# PowerPCB.net
KiCad netlist of a schematic drawn in EAGLE
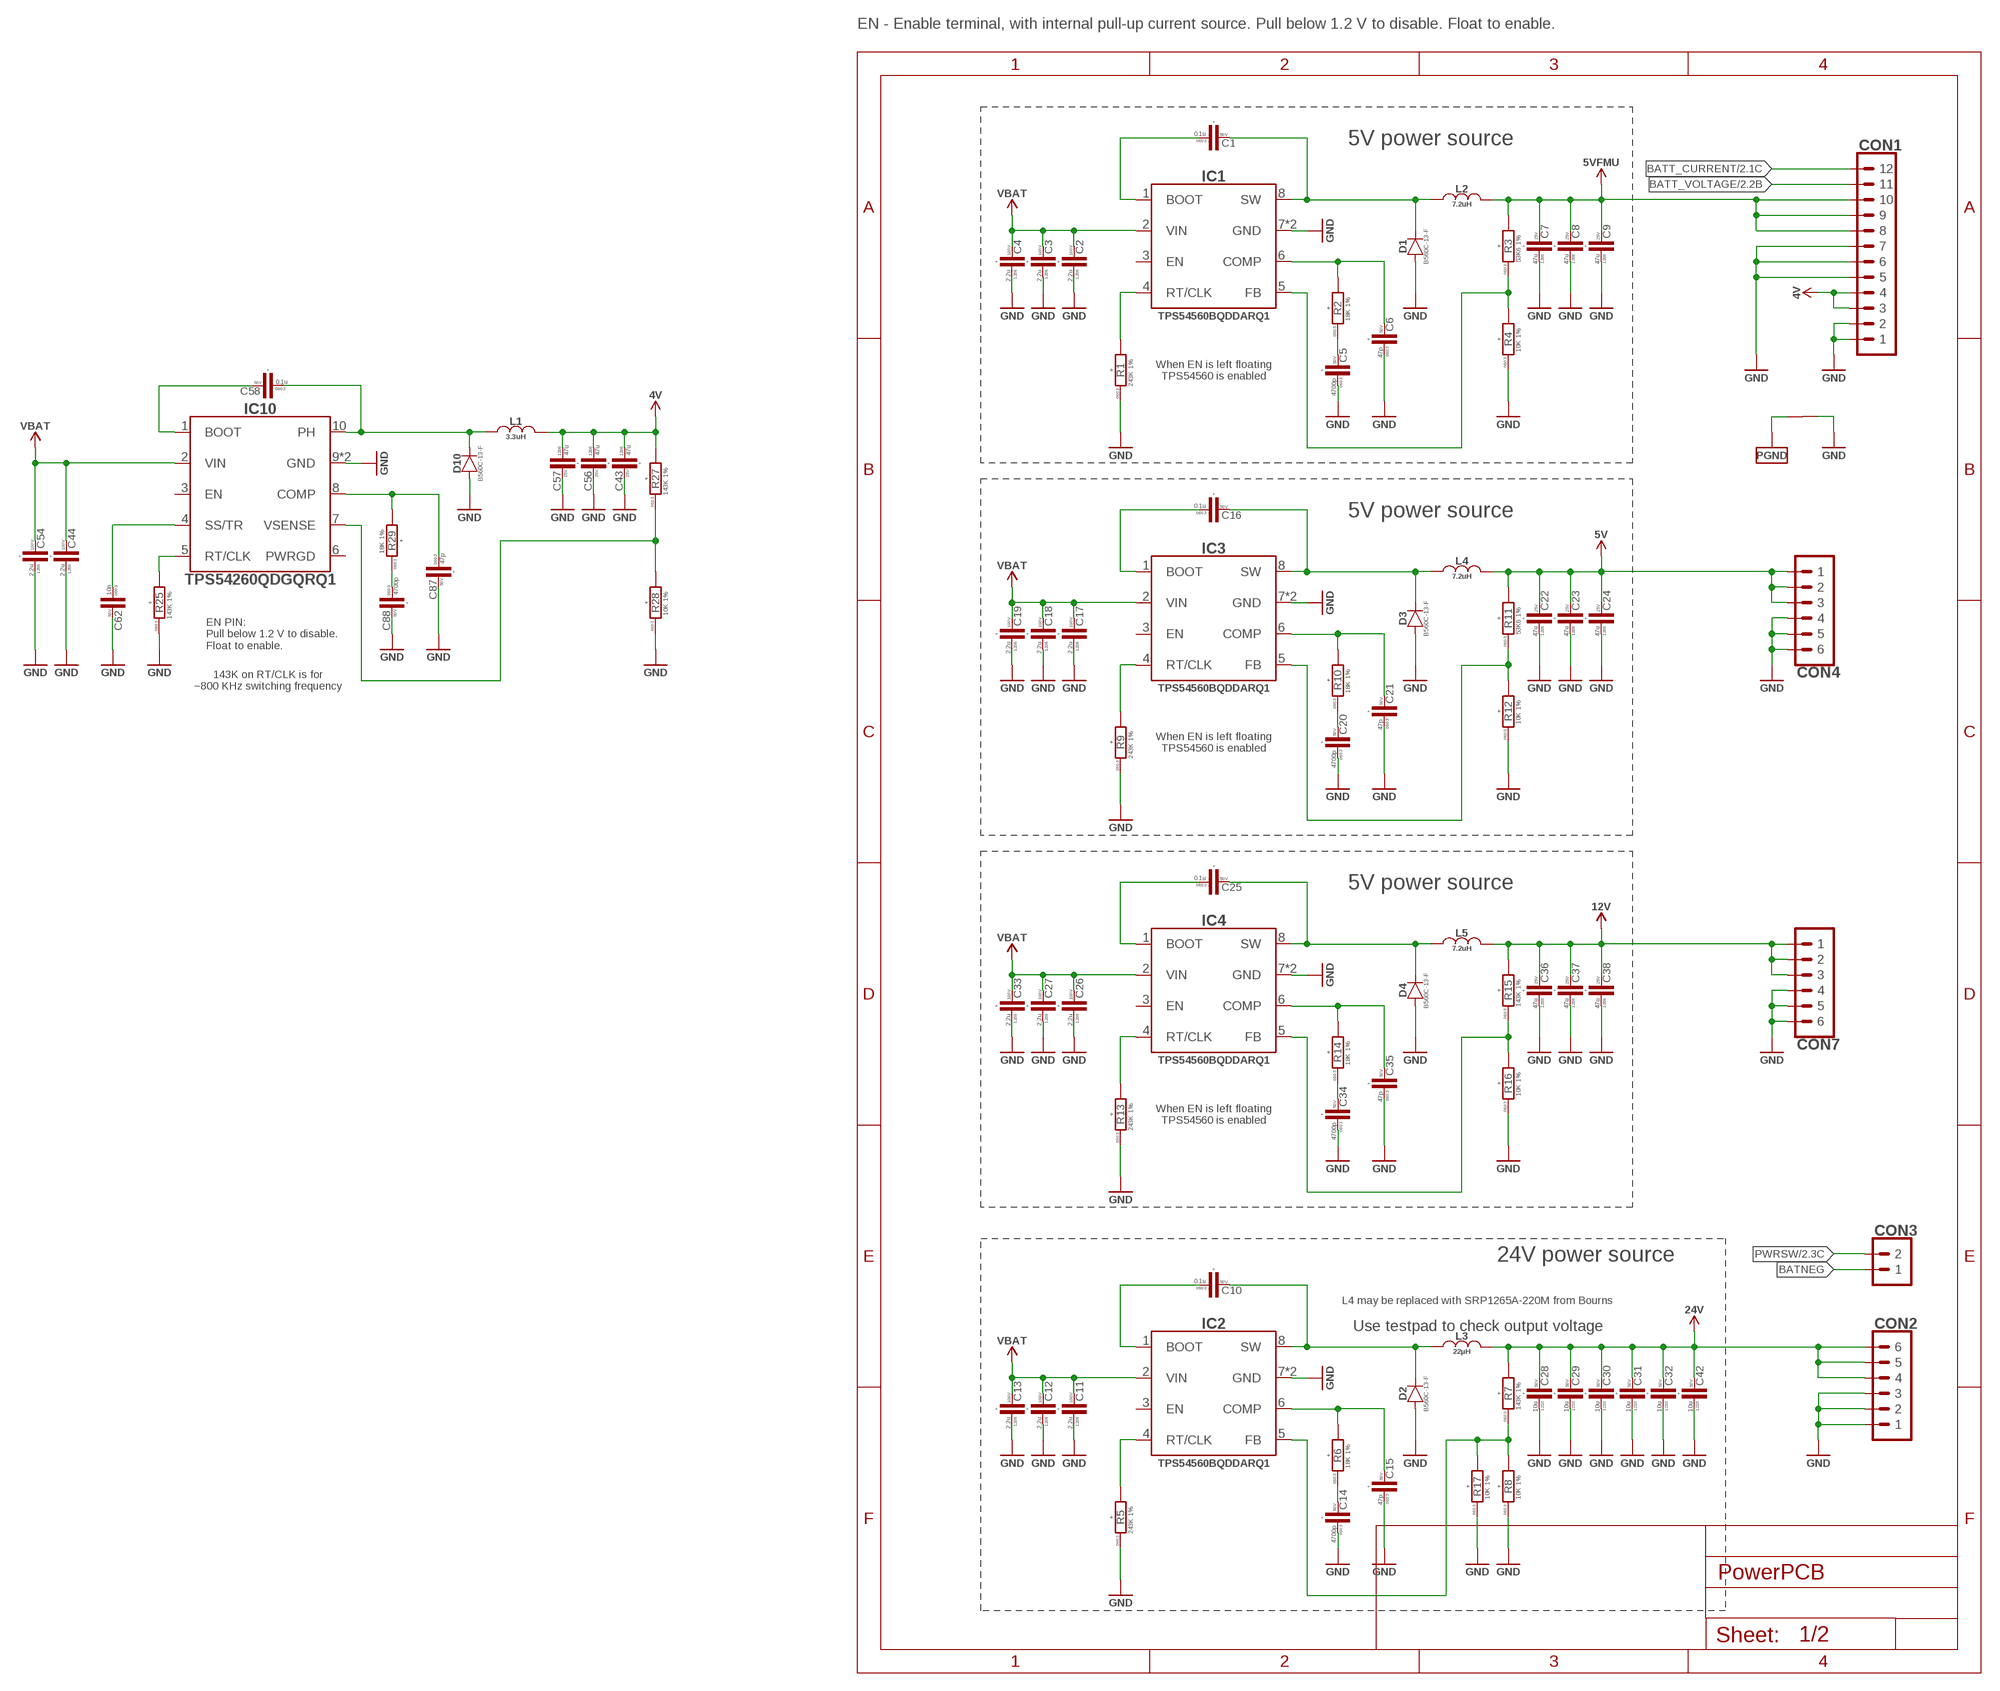
[diagram p0: schematic, sheet 1]
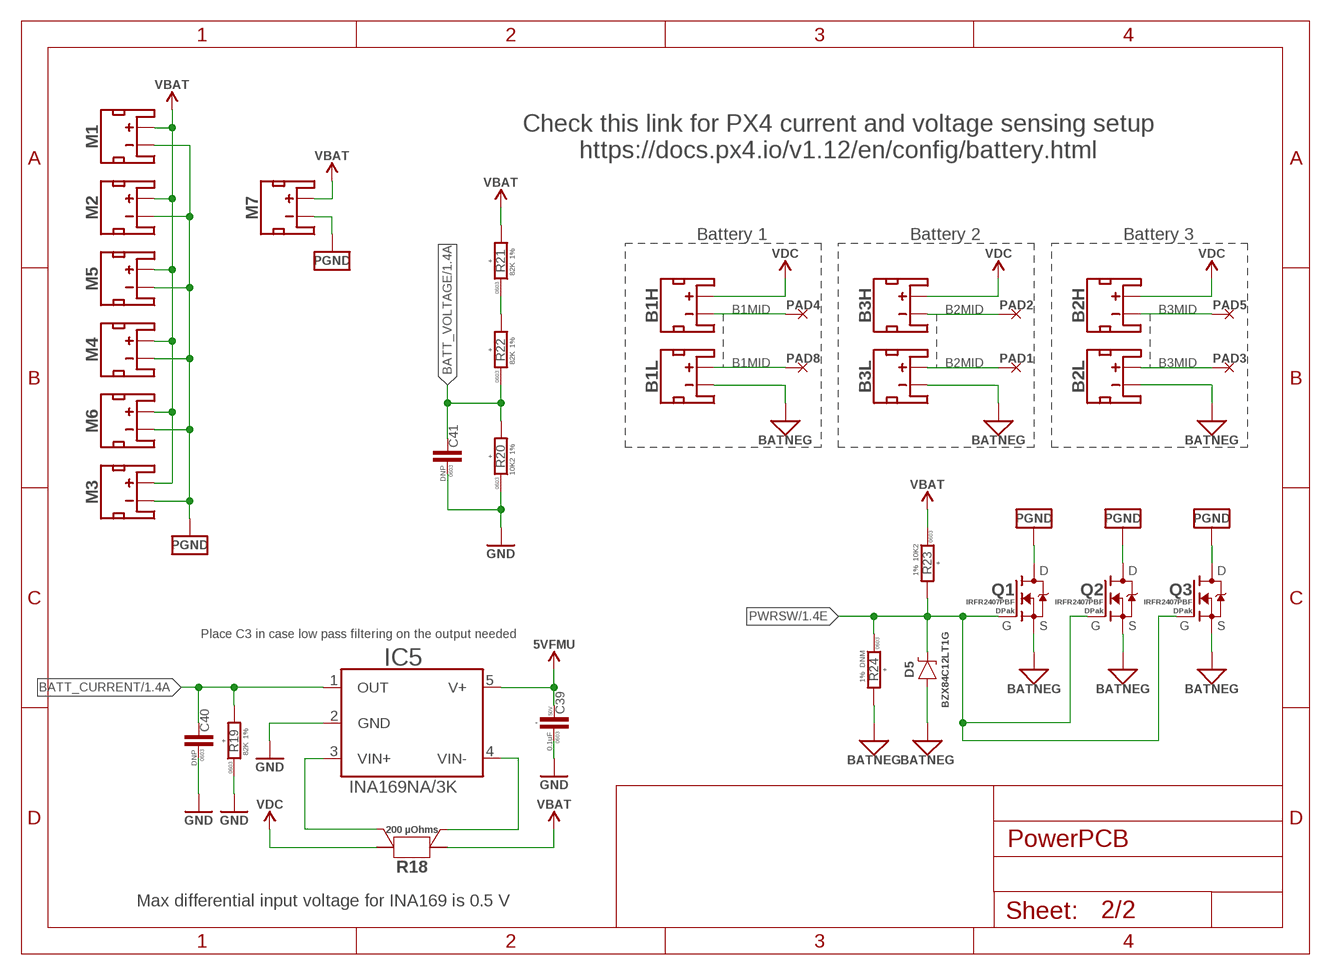
[diagram p1: schematic, sheet 2]

(export (version "E")
  (design (tool "Eeschema 10.0.6"))
  (components
    (comp (ref "B1H")
      (value "BATTERY_CON-XT60PW-M")
      (footprint "eagle-import:XT60PW-M")
      (libsource (lib "eagle-import") (part "BATTERY_CON-XT60PW-M"))
    )
    (comp (ref "B1L")
      (value "BATTERY_CON-XT60PW-M")
      (footprint "eagle-import:XT60PW-M")
      (libsource (lib "eagle-import") (part "BATTERY_CON-XT60PW-M"))
    )
    (comp (ref "B2H")
      (value "BATTERY_CON-XT60PW-M")
      (footprint "eagle-import:XT60PW-M")
      (libsource (lib "eagle-import") (part "BATTERY_CON-XT60PW-M"))
    )
    (comp (ref "B2L")
      (value "BATTERY_CON-XT60PW-M")
      (footprint "eagle-import:XT60PW-M")
      (libsource (lib "eagle-import") (part "BATTERY_CON-XT60PW-M"))
    )
    (comp (ref "B3H")
      (value "BATTERY_CON-XT60PW-M")
      (footprint "eagle-import:XT60PW-M")
      (libsource (lib "eagle-import") (part "BATTERY_CON-XT60PW-M"))
    )
    (comp (ref "B3L")
      (value "BATTERY_CON-XT60PW-M")
      (footprint "eagle-import:XT60PW-M")
      (libsource (lib "eagle-import") (part "BATTERY_CON-XT60PW-M"))
    )
    (comp (ref "C39")
      (value "0.1uF")
      (footprint "eagle-import:C0603")
      (fields
        (field (name "PACKAGE") "0603")
        (field (name "ALLOCATED") "+")
        (field (name "LCSC#") "C14663")
        (field (name "MANF") "YAGEO")
        (field (name "MANF#") "CC0603KRX7R9BB104")
        (field (name "VOLTAGE") "50V")
      )
      (libsource (lib "eagle-import") (part "C-0603"))
    )
    (comp (ref "C40")
      (value "DNP")
      (footprint "eagle-import:C0603")
      (fields (field (name "PACKAGE") "0603"))
      (libsource (lib "eagle-import") (part "C-0603"))
    )
    (comp (ref "C41")
      (value "DNP")
      (footprint "eagle-import:C0603")
      (fields (field (name "PACKAGE") "0603"))
      (libsource (lib "eagle-import") (part "C-0603"))
    )
    (comp (ref "D5")
      (value "BZX84C12")
      (footprint "eagle-import:SOT23")
      (fields (field (name "MANF") "ON Semiconductor") (field (name "MANF#") "BZX84C12LT1G"))
      (libsource (lib "eagle-import") (part "BZX84C12"))
    )
    (comp (ref "IC5")
      (value "INA169")
      (footprint "eagle-import:SOT23-5")
      (fields (field (name "MANF") "Texas Instruments"))
      (libsource (lib "eagle-import") (part "INA169"))
    )
    (comp (ref "M1")
      (value "BATTERY_CON-XT30-RA")
      (footprint "eagle-import:XT30-RA")
      (fields (field (name "MANF") "AMASS"))
      (libsource (lib "eagle-import") (part "BATTERY_CON-XT30-RA"))
    )
    (comp (ref "M2")
      (value "BATTERY_CON-XT30-RA")
      (footprint "eagle-import:XT30-RA")
      (fields (field (name "MANF") "AMASS"))
      (libsource (lib "eagle-import") (part "BATTERY_CON-XT30-RA"))
    )
    (comp (ref "M3")
      (value "BATTERY_CON-XT30-RA")
      (footprint "eagle-import:XT30-RA")
      (fields (field (name "MANF") "AMASS"))
      (libsource (lib "eagle-import") (part "BATTERY_CON-XT30-RA"))
    )
    (comp (ref "M4")
      (value "BATTERY_CON-XT30-RA")
      (footprint "eagle-import:XT30-RA")
      (fields (field (name "MANF") "AMASS"))
      (libsource (lib "eagle-import") (part "BATTERY_CON-XT30-RA"))
    )
    (comp (ref "M5")
      (value "BATTERY_CON-XT30-RA")
      (footprint "eagle-import:XT30-RA")
      (fields (field (name "MANF") "AMASS"))
      (libsource (lib "eagle-import") (part "BATTERY_CON-XT30-RA"))
    )
    (comp (ref "M6")
      (value "BATTERY_CON-XT30-RA")
      (footprint "eagle-import:XT30-RA")
      (fields (field (name "MANF") "AMASS"))
      (libsource (lib "eagle-import") (part "BATTERY_CON-XT30-RA"))
    )
    (comp (ref "M7")
      (value "BATTERY_CON-XT30-RA")
      (footprint "eagle-import:XT30-RA")
      (fields (field (name "MANF") "AMASS"))
      (libsource (lib "eagle-import") (part "BATTERY_CON-XT30-RA"))
    )
    (comp (ref "PAD1")
      (value "PAD-10X4")
      (footprint "eagle-import:10X4")
      (libsource (lib "eagle-import") (part "PAD-10X4"))
    )
    (comp (ref "PAD2")
      (value "PAD-10X4")
      (footprint "eagle-import:10X4")
      (libsource (lib "eagle-import") (part "PAD-10X4"))
    )
    (comp (ref "PAD3")
      (value "PAD-10X4")
      (footprint "eagle-import:10X4")
      (libsource (lib "eagle-import") (part "PAD-10X4"))
    )
    (comp (ref "PAD4")
      (value "PAD-10X4")
      (footprint "eagle-import:10X4")
      (libsource (lib "eagle-import") (part "PAD-10X4"))
    )
    (comp (ref "PAD5")
      (value "PAD-10X4")
      (footprint "eagle-import:10X4")
      (libsource (lib "eagle-import") (part "PAD-10X4"))
    )
    (comp (ref "PAD8")
      (value "PAD-10X4")
      (footprint "eagle-import:10X4")
      (libsource (lib "eagle-import") (part "PAD-10X4"))
    )
    (comp (ref "Q1")
      (value "IRFR2407PBF")
      (footprint "eagle-import:D-PAK")
      (fields
        (field (name "MANF#") "IRFR2407PBF")
        (field (name "PACKAGE") "DPak")
        (field (name "MANF") "International Rectifier")
      )
      (libsource (lib "eagle-import") (part "IRFR2407PBF"))
    )
    (comp (ref "Q2")
      (value "IRFR2407PBF")
      (footprint "eagle-import:D-PAK")
      (fields
        (field (name "MANF#") "IRFR2407PBF")
        (field (name "PACKAGE") "DPak")
        (field (name "MANF") "International Rectifier")
      )
      (libsource (lib "eagle-import") (part "IRFR2407PBF"))
    )
    (comp (ref "Q3")
      (value "IRFR2407PBF")
      (footprint "eagle-import:D-PAK")
      (fields
        (field (name "MANF#") "IRFR2407PBF")
        (field (name "PACKAGE") "DPak")
        (field (name "MANF") "International Rectifier")
      )
      (libsource (lib "eagle-import") (part "IRFR2407PBF"))
    )
    (comp (ref "R18")
      (value "200 µOhms")
      (footprint "eagle-import:R3920-KELVIN")
      (fields
        (field (name "MANF") "Bourns Inc")
        (field (name "POWER") "12W")
        (field (name "TOLERANCE") "±1%")
      )
      (libsource (lib "eagle-import") (part "CURRENT_SHUNT_KELVIN-3920-KELVIN-0.0002R"))
    )
    (comp (ref "R19")
      (value "82K")
      (footprint "eagle-import:R0603")
      (fields
        (field (name "PACKAGE") "0603")
        (field (name "TOLERANCE") "1%")
        (field (name "ALLOCATED") "+")
        (field (name "LCSC#") "C23254")
        (field (name "MANF") "UNI-ROYAL(Uniroyal Elec)")
        (field (name "MANF#") "0603WAF8202T5E")
      )
      (libsource (lib "eagle-import") (part "R-0603-1%"))
    )
    (comp (ref "R20")
      (value "10K2")
      (footprint "eagle-import:R0603")
      (fields
        (field (name "PACKAGE") "0603")
        (field (name "TOLERANCE") "1%")
        (field (name "ALLOCATED") "+")
        (field (name "LCSC#") "C22772")
        (field (name "MANF") "UNI-ROYAL(Uniroyal Elec)")
        (field (name "MANF#") "0603WAF1022T5E")
      )
      (libsource (lib "eagle-import") (part "R-0603-1%"))
    )
    (comp (ref "R21")
      (value "82K")
      (footprint "eagle-import:R0603")
      (fields
        (field (name "PACKAGE") "0603")
        (field (name "TOLERANCE") "1%")
        (field (name "ALLOCATED") "+")
        (field (name "LCSC#") "C23254")
        (field (name "MANF") "UNI-ROYAL(Uniroyal Elec)")
        (field (name "MANF#") "0603WAF8202T5E")
      )
      (libsource (lib "eagle-import") (part "R-0603-1%"))
    )
    (comp (ref "R22")
      (value "82K")
      (footprint "eagle-import:R0603")
      (fields
        (field (name "PACKAGE") "0603")
        (field (name "TOLERANCE") "1%")
        (field (name "ALLOCATED") "+")
        (field (name "LCSC#") "C23254")
        (field (name "MANF") "UNI-ROYAL(Uniroyal Elec)")
        (field (name "MANF#") "0603WAF8202T5E")
      )
      (libsource (lib "eagle-import") (part "R-0603-1%"))
    )
    (comp (ref "R23")
      (value "10K2")
      (footprint "eagle-import:R0603")
      (fields
        (field (name "PACKAGE") "0603")
        (field (name "TOLERANCE") "1%")
        (field (name "ALLOCATED") "+")
        (field (name "LCSC#") "C22772")
        (field (name "MANF") "UNI-ROYAL(Uniroyal Elec)")
        (field (name "MANF#") "0603WAF1022T5E")
      )
      (libsource (lib "eagle-import") (part "R-0603-1%"))
    )
    (comp (ref "R24")
      (value "DNM")
      (footprint "eagle-import:R0603")
      (fields
        (field (name "PACKAGE") "0603")
        (field (name "TOLERANCE") "1%")
        (field (name "ALLOCATED") "+")
        (field (name "LCSC#") "C22772")
        (field (name "MANF") "UNI-ROYAL(Uniroyal Elec)")
        (field (name "MANF#") "0603WAF1022T5E")
      )
      (libsource (lib "eagle-import") (part "R-0603-1%"))
    )
    (comp (ref "C1")
      (value "0.1u")
      (footprint "eagle-import:C0603")
      (fields
        (field (name "PACKAGE") "0603")
        (field (name "ALLOCATED") "+")
        (field (name "LCSC#") "C14663")
        (field (name "MANF") "YAGEO")
        (field (name "MANF#") "CC0603KRX7R9BB104")
        (field (name "VOLTAGE") "50V")
      )
      (libsource (lib "eagle-import") (part "C-0603"))
    )
    (comp (ref "C2")
      (value "2.2u")
      (footprint "eagle-import:C1206")
      (fields
        (field (name "PACKAGE") "1206")
        (field (name "ALLOCATED") "+")
        (field (name "LCSC#") "C170101")
        (field (name "MANF") "Samsung Electro-Mechanics")
        (field (name "MANF#") "CL31B225KCHSNNE")
        (field (name "VOLTAGE") "100V")
      )
      (libsource (lib "eagle-import") (part "C-1206"))
    )
    (comp (ref "C3")
      (value "2.2u")
      (footprint "eagle-import:C1206")
      (fields
        (field (name "PACKAGE") "1206")
        (field (name "ALLOCATED") "+")
        (field (name "LCSC#") "C170101")
        (field (name "MANF") "Samsung Electro-Mechanics")
        (field (name "MANF#") "CL31B225KCHSNNE")
        (field (name "VOLTAGE") "100V")
      )
      (libsource (lib "eagle-import") (part "C-1206"))
    )
    (comp (ref "C4")
      (value "2.2u")
      (footprint "eagle-import:C1206")
      (fields
        (field (name "PACKAGE") "1206")
        (field (name "ALLOCATED") "+")
        (field (name "LCSC#") "C170101")
        (field (name "MANF") "Samsung Electro-Mechanics")
        (field (name "MANF#") "CL31B225KCHSNNE")
        (field (name "VOLTAGE") "100V")
      )
      (libsource (lib "eagle-import") (part "C-1206"))
    )
    (comp (ref "C5")
      (value "4700p")
      (footprint "eagle-import:C0603")
      (fields
        (field (name "PACKAGE") "0603")
        (field (name "ALLOCATED") "+")
        (field (name "LCSC#") "C106218")
        (field (name "MANF") "YAGEO")
        (field (name "MANF#") "CC0603KRX7R9BB472")
        (field (name "VOLTAGE") "50V")
      )
      (libsource (lib "eagle-import") (part "C-0603"))
    )
    (comp (ref "C6")
      (value "47p")
      (footprint "eagle-import:C0603")
      (fields
        (field (name "PACKAGE") "0603")
        (field (name "ALLOCATED") "+")
        (field (name "LCSC#") "C1671")
        (field (name "MANF") "Samsung Electro-Mechanics")
        (field (name "MANF#") "CL10C470JB8NNNC")
        (field (name "VOLTAGE") "50V")
      )
      (libsource (lib "eagle-import") (part "C-0603"))
    )
    (comp (ref "C7")
      (value "47u")
      (footprint "eagle-import:C1206")
      (fields
        (field (name "PACKAGE") "1206")
        (field (name "ALLOCATED") "+")
        (field (name "LCSC#") "C403725")
        (field (name "MANF") "Murata Electronics")
        (field (name "MANF#") "GRM31CR61E476ME44L")
        (field (name "VOLTAGE") "25V")
      )
      (libsource (lib "eagle-import") (part "C-1206"))
    )
    (comp (ref "C8")
      (value "47u")
      (footprint "eagle-import:C1206")
      (fields
        (field (name "PACKAGE") "1206")
        (field (name "ALLOCATED") "+")
        (field (name "LCSC#") "C403725")
        (field (name "MANF") "Murata Electronics")
        (field (name "MANF#") "GRM31CR61E476ME44L")
        (field (name "VOLTAGE") "25V")
      )
      (libsource (lib "eagle-import") (part "C-1206"))
    )
    (comp (ref "C9")
      (value "47u")
      (footprint "eagle-import:C1206")
      (fields
        (field (name "PACKAGE") "1206")
        (field (name "ALLOCATED") "+")
        (field (name "LCSC#") "C403725")
        (field (name "MANF") "Murata Electronics")
        (field (name "MANF#") "GRM31CR61E476ME44L")
        (field (name "VOLTAGE") "25V")
      )
      (libsource (lib "eagle-import") (part "C-1206"))
    )
    (comp (ref "C10")
      (value "0.1u")
      (footprint "eagle-import:C0603")
      (fields
        (field (name "PACKAGE") "0603")
        (field (name "ALLOCATED") "+")
        (field (name "LCSC#") "C14663")
        (field (name "MANF") "YAGEO")
        (field (name "MANF#") "CC0603KRX7R9BB104")
        (field (name "VOLTAGE") "50V")
      )
      (libsource (lib "eagle-import") (part "C-0603"))
    )
    (comp (ref "C11")
      (value "2.2u")
      (footprint "eagle-import:C1206")
      (fields
        (field (name "PACKAGE") "1206")
        (field (name "ALLOCATED") "+")
        (field (name "LCSC#") "C170101")
        (field (name "MANF") "Samsung Electro-Mechanics")
        (field (name "MANF#") "CL31B225KCHSNNE")
        (field (name "VOLTAGE") "100V")
      )
      (libsource (lib "eagle-import") (part "C-1206"))
    )
    (comp (ref "C12")
      (value "2.2u")
      (footprint "eagle-import:C1206")
      (fields
        (field (name "PACKAGE") "1206")
        (field (name "ALLOCATED") "+")
        (field (name "LCSC#") "C170101")
        (field (name "MANF") "Samsung Electro-Mechanics")
        (field (name "MANF#") "CL31B225KCHSNNE")
        (field (name "VOLTAGE") "100V")
      )
      (libsource (lib "eagle-import") (part "C-1206"))
    )
    (comp (ref "C13")
      (value "2.2u")
      (footprint "eagle-import:C1206")
      (fields
        (field (name "PACKAGE") "1206")
        (field (name "ALLOCATED") "+")
        (field (name "LCSC#") "C170101")
        (field (name "MANF") "Samsung Electro-Mechanics")
        (field (name "MANF#") "CL31B225KCHSNNE")
        (field (name "VOLTAGE") "100V")
      )
      (libsource (lib "eagle-import") (part "C-1206"))
    )
    (comp (ref "C14")
      (value "4700p")
      (footprint "eagle-import:C0603")
      (fields
        (field (name "PACKAGE") "0603")
        (field (name "ALLOCATED") "+")
        (field (name "LCSC#") "C106218")
        (field (name "MANF") "YAGEO")
        (field (name "MANF#") "CC0603KRX7R9BB472")
        (field (name "VOLTAGE") "50V")
      )
      (libsource (lib "eagle-import") (part "C-0603"))
    )
    (comp (ref "C15")
      (value "47p")
      (footprint "eagle-import:C0603")
      (fields
        (field (name "PACKAGE") "0603")
        (field (name "ALLOCATED") "+")
        (field (name "LCSC#") "C1671")
        (field (name "MANF") "Samsung Electro-Mechanics")
        (field (name "MANF#") "CL10C470JB8NNNC")
        (field (name "VOLTAGE") "50V")
      )
      (libsource (lib "eagle-import") (part "C-0603"))
    )
    (comp (ref "C16")
      (value "0.1u")
      (footprint "eagle-import:C0603")
      (fields
        (field (name "PACKAGE") "0603")
        (field (name "ALLOCATED") "+")
        (field (name "LCSC#") "C14663")
        (field (name "MANF") "YAGEO")
        (field (name "MANF#") "CC0603KRX7R9BB104")
        (field (name "VOLTAGE") "50V")
      )
      (libsource (lib "eagle-import") (part "C-0603"))
    )
    (comp (ref "C17")
      (value "2.2u")
      (footprint "eagle-import:C1206")
      (fields
        (field (name "PACKAGE") "1206")
        (field (name "ALLOCATED") "+")
        (field (name "LCSC#") "C170101")
        (field (name "MANF") "Samsung Electro-Mechanics")
        (field (name "MANF#") "CL31B225KCHSNNE")
        (field (name "VOLTAGE") "100V")
      )
      (libsource (lib "eagle-import") (part "C-1206"))
    )
    (comp (ref "C18")
      (value "2.2u")
      (footprint "eagle-import:C1206")
      (fields
        (field (name "PACKAGE") "1206")
        (field (name "ALLOCATED") "+")
        (field (name "LCSC#") "C170101")
        (field (name "MANF") "Samsung Electro-Mechanics")
        (field (name "MANF#") "CL31B225KCHSNNE")
        (field (name "VOLTAGE") "100V")
      )
      (libsource (lib "eagle-import") (part "C-1206"))
    )
    (comp (ref "C19")
      (value "2.2u")
      (footprint "eagle-import:C1206")
      (fields
        (field (name "PACKAGE") "1206")
        (field (name "ALLOCATED") "+")
        (field (name "LCSC#") "C170101")
        (field (name "MANF") "Samsung Electro-Mechanics")
        (field (name "MANF#") "CL31B225KCHSNNE")
        (field (name "VOLTAGE") "100V")
      )
      (libsource (lib "eagle-import") (part "C-1206"))
    )
    (comp (ref "C20")
      (value "4700p")
      (footprint "eagle-import:C0603")
      (fields
        (field (name "PACKAGE") "0603")
        (field (name "ALLOCATED") "+")
        (field (name "LCSC#") "C106218")
        (field (name "MANF") "YAGEO")
        (field (name "MANF#") "CC0603KRX7R9BB472")
        (field (name "VOLTAGE") "50V")
      )
      (libsource (lib "eagle-import") (part "C-0603"))
    )
    (comp (ref "C21")
      (value "47p")
      (footprint "eagle-import:C0603")
      (fields
        (field (name "PACKAGE") "0603")
        (field (name "ALLOCATED") "+")
        (field (name "LCSC#") "C1671")
        (field (name "MANF") "Samsung Electro-Mechanics")
        (field (name "MANF#") "CL10C470JB8NNNC")
        (field (name "VOLTAGE") "50V")
      )
      (libsource (lib "eagle-import") (part "C-0603"))
    )
    (comp (ref "C22")
      (value "47u")
      (footprint "eagle-import:C1206")
      (fields
        (field (name "PACKAGE") "1206")
        (field (name "ALLOCATED") "+")
        (field (name "LCSC#") "C403725")
        (field (name "MANF") "Murata Electronics")
        (field (name "MANF#") "GRM31CR61E476ME44L")
        (field (name "VOLTAGE") "25V")
      )
      (libsource (lib "eagle-import") (part "C-1206"))
    )
    (comp (ref "C23")
      (value "47u")
      (footprint "eagle-import:C1206")
      (fields
        (field (name "PACKAGE") "1206")
        (field (name "ALLOCATED") "+")
        (field (name "LCSC#") "C403725")
        (field (name "MANF") "Murata Electronics")
        (field (name "MANF#") "GRM31CR61E476ME44L")
        (field (name "VOLTAGE") "25V")
      )
      (libsource (lib "eagle-import") (part "C-1206"))
    )
    (comp (ref "C24")
      (value "47u")
      (footprint "eagle-import:C1206")
      (fields
        (field (name "PACKAGE") "1206")
        (field (name "ALLOCATED") "+")
        (field (name "LCSC#") "C403725")
        (field (name "MANF") "Murata Electronics")
        (field (name "MANF#") "GRM31CR61E476ME44L")
        (field (name "VOLTAGE") "25V")
      )
      (libsource (lib "eagle-import") (part "C-1206"))
    )
    (comp (ref "C25")
      (value "0.1u")
      (footprint "eagle-import:C0603")
      (fields
        (field (name "PACKAGE") "0603")
        (field (name "ALLOCATED") "+")
        (field (name "LCSC#") "C14663")
        (field (name "MANF") "YAGEO")
        (field (name "MANF#") "CC0603KRX7R9BB104")
        (field (name "VOLTAGE") "50V")
      )
      (libsource (lib "eagle-import") (part "C-0603"))
    )
    (comp (ref "C26")
      (value "2.2u")
      (footprint "eagle-import:C1206")
      (fields
        (field (name "PACKAGE") "1206")
        (field (name "ALLOCATED") "+")
        (field (name "LCSC#") "C170101")
        (field (name "MANF") "Samsung Electro-Mechanics")
        (field (name "MANF#") "CL31B225KCHSNNE")
        (field (name "VOLTAGE") "100V")
      )
      (libsource (lib "eagle-import") (part "C-1206"))
    )
    (comp (ref "C27")
      (value "2.2u")
      (footprint "eagle-import:C1206")
      (fields
        (field (name "PACKAGE") "1206")
        (field (name "ALLOCATED") "+")
        (field (name "LCSC#") "C170101")
        (field (name "MANF") "Samsung Electro-Mechanics")
        (field (name "MANF#") "CL31B225KCHSNNE")
        (field (name "VOLTAGE") "100V")
      )
      (libsource (lib "eagle-import") (part "C-1206"))
    )
    (comp (ref "C28")
      (value "10u")
      (footprint "eagle-import:C1210")
      (fields
        (field (name "PACKAGE") "1210")
        (field (name "ALLOCATED") "+")
        (field (name "LCSC#") "C77102")
        (field (name "MANF") "Murata Electronics")
        (field (name "MANF#") "GRM32ER71H106K")
        (field (name "VOLTAGE") "50V")
      )
      (libsource (lib "eagle-import") (part "C-1210"))
    )
    (comp (ref "C29")
      (value "10u")
      (footprint "eagle-import:C1210")
      (fields
        (field (name "PACKAGE") "1210")
        (field (name "ALLOCATED") "+")
        (field (name "LCSC#") "C77102")
        (field (name "MANF") "Murata Electronics")
        (field (name "MANF#") "GRM32ER71H106K")
        (field (name "VOLTAGE") "50V")
      )
      (libsource (lib "eagle-import") (part "C-1210"))
    )
    (comp (ref "C30")
      (value "10u")
      (footprint "eagle-import:C1210")
      (fields
        (field (name "PACKAGE") "1210")
        (field (name "ALLOCATED") "+")
        (field (name "LCSC#") "C77102")
        (field (name "MANF") "Murata Electronics")
        (field (name "MANF#") "GRM32ER71H106K")
        (field (name "VOLTAGE") "50V")
      )
      (libsource (lib "eagle-import") (part "C-1210"))
    )
    (comp (ref "C31")
      (value "10u")
      (footprint "eagle-import:C1210")
      (fields
        (field (name "PACKAGE") "1210")
        (field (name "ALLOCATED") "+")
        (field (name "LCSC#") "C77102")
        (field (name "MANF") "Murata Electronics")
        (field (name "MANF#") "GRM32ER71H106K")
        (field (name "VOLTAGE") "50V")
      )
      (libsource (lib "eagle-import") (part "C-1210"))
    )
    (comp (ref "C32")
      (value "10u")
      (footprint "eagle-import:C1210")
      (fields
        (field (name "PACKAGE") "1210")
        (field (name "ALLOCATED") "+")
        (field (name "LCSC#") "C77102")
        (field (name "MANF") "Murata Electronics")
        (field (name "MANF#") "GRM32ER71H106K")
        (field (name "VOLTAGE") "50V")
      )
      (libsource (lib "eagle-import") (part "C-1210"))
    )
    (comp (ref "C33")
      (value "2.2u")
      (footprint "eagle-import:C1206")
      (fields
        (field (name "PACKAGE") "1206")
        (field (name "ALLOCATED") "+")
        (field (name "LCSC#") "C170101")
        (field (name "MANF") "Samsung Electro-Mechanics")
        (field (name "MANF#") "CL31B225KCHSNNE")
        (field (name "VOLTAGE") "100V")
      )
      (libsource (lib "eagle-import") (part "C-1206"))
    )
    (comp (ref "C34")
      (value "4700p")
      (footprint "eagle-import:C0603")
      (fields
        (field (name "PACKAGE") "0603")
        (field (name "ALLOCATED") "+")
        (field (name "LCSC#") "C106218")
        (field (name "MANF") "YAGEO")
        (field (name "MANF#") "CC0603KRX7R9BB472")
        (field (name "VOLTAGE") "50V")
      )
      (libsource (lib "eagle-import") (part "C-0603"))
    )
    (comp (ref "C35")
      (value "47p")
      (footprint "eagle-import:C0603")
      (fields
        (field (name "PACKAGE") "0603")
        (field (name "ALLOCATED") "+")
        (field (name "LCSC#") "C1671")
        (field (name "MANF") "Samsung Electro-Mechanics")
        (field (name "MANF#") "CL10C470JB8NNNC")
        (field (name "VOLTAGE") "50V")
      )
      (libsource (lib "eagle-import") (part "C-0603"))
    )
    (comp (ref "C36")
      (value "47u")
      (footprint "eagle-import:C1206")
      (fields
        (field (name "PACKAGE") "1206")
        (field (name "ALLOCATED") "+")
        (field (name "LCSC#") "C403725")
        (field (name "MANF") "Murata Electronics")
        (field (name "MANF#") "GRM31CR61E476ME44L")
        (field (name "VOLTAGE") "25V")
      )
      (libsource (lib "eagle-import") (part "C-1206"))
    )
    (comp (ref "C37")
      (value "47u")
      (footprint "eagle-import:C1206")
      (fields
        (field (name "PACKAGE") "1206")
        (field (name "ALLOCATED") "+")
        (field (name "LCSC#") "C403725")
        (field (name "MANF") "Murata Electronics")
        (field (name "MANF#") "GRM31CR61E476ME44L")
        (field (name "VOLTAGE") "25V")
      )
      (libsource (lib "eagle-import") (part "C-1206"))
    )
    (comp (ref "C38")
      (value "47u")
      (footprint "eagle-import:C1206")
      (fields
        (field (name "PACKAGE") "1206")
        (field (name "ALLOCATED") "+")
        (field (name "LCSC#") "C403725")
        (field (name "MANF") "Murata Electronics")
        (field (name "MANF#") "GRM31CR61E476ME44L")
        (field (name "VOLTAGE") "25V")
      )
      (libsource (lib "eagle-import") (part "C-1206"))
    )
    (comp (ref "C42")
      (value "10u")
      (footprint "eagle-import:C1210")
      (fields
        (field (name "PACKAGE") "1210")
        (field (name "ALLOCATED") "+")
        (field (name "LCSC#") "C77102")
        (field (name "MANF") "Murata Electronics")
        (field (name "MANF#") "GRM32ER71H106K")
        (field (name "VOLTAGE") "50V")
      )
      (libsource (lib "eagle-import") (part "C-1210"))
    )
    (comp (ref "C43")
      (value "47u")
      (footprint "eagle-import:C1206")
      (fields
        (field (name "PACKAGE") "1206")
        (field (name "ALLOCATED") "+")
        (field (name "LCSC#") "C403725")
        (field (name "MANF") "Murata Electronics")
        (field (name "MANF#") "GRM31CR61E476ME44L")
        (field (name "VOLTAGE") "25V")
      )
      (libsource (lib "eagle-import") (part "C-1206"))
    )
    (comp (ref "C44")
      (value "2.2u")
      (footprint "eagle-import:C1206")
      (fields
        (field (name "PACKAGE") "1206")
        (field (name "ALLOCATED") "+")
        (field (name "LCSC#") "C170101")
        (field (name "MANF") "Samsung Electro-Mechanics")
        (field (name "MANF#") "CL31B225KCHSNNE")
        (field (name "VOLTAGE") "100V")
      )
      (libsource (lib "eagle-import") (part "C-1206"))
    )
    (comp (ref "C54")
      (value "2.2u")
      (footprint "eagle-import:C1206")
      (fields
        (field (name "PACKAGE") "1206")
        (field (name "ALLOCATED") "+")
        (field (name "LCSC#") "C170101")
        (field (name "MANF") "Samsung Electro-Mechanics")
        (field (name "MANF#") "CL31B225KCHSNNE")
        (field (name "VOLTAGE") "100V")
      )
      (libsource (lib "eagle-import") (part "C-1206"))
    )
    (comp (ref "C56")
      (value "47u")
      (footprint "eagle-import:C1206")
      (fields
        (field (name "PACKAGE") "1206")
        (field (name "ALLOCATED") "+")
        (field (name "LCSC#") "C403725")
        (field (name "MANF") "Murata Electronics")
        (field (name "MANF#") "GRM31CR61E476ME44L")
        (field (name "VOLTAGE") "25V")
      )
      (libsource (lib "eagle-import") (part "C-1206"))
    )
    (comp (ref "C57")
      (value "47u")
      (footprint "eagle-import:C1206")
      (fields
        (field (name "PACKAGE") "1206")
        (field (name "ALLOCATED") "+")
        (field (name "LCSC#") "C403725")
        (field (name "MANF") "Murata Electronics")
        (field (name "MANF#") "GRM31CR61E476ME44L")
        (field (name "VOLTAGE") "25V")
      )
      (libsource (lib "eagle-import") (part "C-1206"))
    )
    (comp (ref "C58")
      (value "0.1u")
      (footprint "eagle-import:C0603")
      (fields
        (field (name "PACKAGE") "0603")
        (field (name "ALLOCATED") "+")
        (field (name "LCSC#") "C14663")
        (field (name "MANF") "YAGEO")
        (field (name "MANF#") "CC0603KRX7R9BB104")
        (field (name "VOLTAGE") "50V")
      )
      (libsource (lib "eagle-import") (part "C-0603"))
    )
    (comp (ref "C62")
      (value "10n")
      (footprint "eagle-import:C0603")
      (fields (field (name "PACKAGE") "0603") (field (name "VOLTAGE") "50V"))
      (libsource (lib "eagle-import") (part "C-0603"))
    )
    (comp (ref "C87")
      (value "47p")
      (footprint "eagle-import:C0603")
      (fields
        (field (name "PACKAGE") "0603")
        (field (name "ALLOCATED") "+")
        (field (name "LCSC#") "C1671")
        (field (name "MANF") "Samsung Electro-Mechanics")
        (field (name "MANF#") "CL10C470JB8NNNC")
        (field (name "VOLTAGE") "50V")
      )
      (libsource (lib "eagle-import") (part "C-0603"))
    )
    (comp (ref "C88")
      (value "4700p")
      (footprint "eagle-import:C0603")
      (fields
        (field (name "PACKAGE") "0603")
        (field (name "ALLOCATED") "+")
        (field (name "LCSC#") "C106218")
        (field (name "MANF") "YAGEO")
        (field (name "MANF#") "CC0603KRX7R9BB472")
        (field (name "VOLTAGE") "50V")
      )
      (libsource (lib "eagle-import") (part "C-0603"))
    )
    (comp (ref "CON1")
      (value "PINHEAD_1X12-2.54-FEMALE")
      (footprint "eagle-import:1X12-PTH-2.54-FEMALE")
      (libsource (lib "eagle-import") (part "PINHEAD_1X12-2.54-FEMALE"))
    )
    (comp (ref "CON2")
      (value "PINHEAD_1X06-2.54-FEMALE")
      (footprint "eagle-import:1X06-PTH-2.54-FEMALE")
      (libsource (lib "eagle-import") (part "PINHEAD_1X06-2.54-FEMALE"))
    )
    (comp (ref "CON3")
      (value "PINHEAD_1X02-2.54-FEMALE")
      (footprint "eagle-import:1X02-PTH-2.54-FEMALE")
      (libsource (lib "eagle-import") (part "PINHEAD_1X02-2.54-FEMALE"))
    )
    (comp (ref "CON4")
      (value "PINHEAD_1X06-2.54-FEMALE")
      (footprint "eagle-import:1X06-PTH-2.54-FEMALE")
      (libsource (lib "eagle-import") (part "PINHEAD_1X06-2.54-FEMALE"))
    )
    (comp (ref "CON7")
      (value "PINHEAD_1X06-2.54-FEMALE")
      (footprint "eagle-import:1X06-PTH-2.54-FEMALE")
      (libsource (lib "eagle-import") (part "PINHEAD_1X06-2.54-FEMALE"))
    )
    (comp (ref "D1")
      (value "B560C")
      (footprint "eagle-import:DO-214AB(SMC)")
      (fields (field (name "MANF#") "B560C-13-F") (field (name "MANF") "Diodes Incorporated"))
      (libsource (lib "eagle-import") (part "B560C"))
    )
    (comp (ref "D2")
      (value "B560C")
      (footprint "eagle-import:DO-214AB(SMC)")
      (fields (field (name "MANF#") "B560C-13-F") (field (name "MANF") "Diodes Incorporated"))
      (libsource (lib "eagle-import") (part "B560C"))
    )
    (comp (ref "D3")
      (value "B560C")
      (footprint "eagle-import:DO-214AB(SMC)")
      (fields (field (name "MANF#") "B560C-13-F") (field (name "MANF") "Diodes Incorporated"))
      (libsource (lib "eagle-import") (part "B560C"))
    )
    (comp (ref "D4")
      (value "B560C")
      (footprint "eagle-import:DO-214AB(SMC)")
      (fields (field (name "MANF#") "B560C-13-F") (field (name "MANF") "Diodes Incorporated"))
      (libsource (lib "eagle-import") (part "B560C"))
    )
    (comp (ref "D10")
      (value "B560C")
      (footprint "eagle-import:DO-214AB(SMC)")
      (fields (field (name "MANF#") "B560C-13-F") (field (name "MANF") "Diodes Incorporated"))
      (libsource (lib "eagle-import") (part "B560C"))
    )
    (comp (ref "IC1")
      (value "TPS54560B")
      (footprint "eagle-import:SOIC8-POWERPAD")
      (fields (field (name "MANF#") "TPS54560BQDDARQ1") (field (name "MANF") "Texas Instruments"))
      (libsource (lib "eagle-import") (part "TPS54560B"))
    )
    (comp (ref "IC2")
      (value "TPS54560B")
      (footprint "eagle-import:SOIC8-POWERPAD")
      (fields (field (name "MANF#") "TPS54560BQDDARQ1") (field (name "MANF") "Texas Instruments"))
      (libsource (lib "eagle-import") (part "TPS54560B"))
    )
    (comp (ref "IC3")
      (value "TPS54560B")
      (footprint "eagle-import:SOIC8-POWERPAD")
      (fields (field (name "MANF#") "TPS54560BQDDARQ1") (field (name "MANF") "Texas Instruments"))
      (libsource (lib "eagle-import") (part "TPS54560B"))
    )
    (comp (ref "IC4")
      (value "TPS54560B")
      (footprint "eagle-import:SOIC8-POWERPAD")
      (fields (field (name "MANF#") "TPS54560BQDDARQ1") (field (name "MANF") "Texas Instruments"))
      (libsource (lib "eagle-import") (part "TPS54560B"))
    )
    (comp (ref "IC10")
      (value "TPS54260")
      (footprint "eagle-import:MSOP10")
      (fields
        (field (name "MANF#") "TPS54260DGQR")
        (field (name "MANF") "Texas Instruments")
        (field (name "DIGIKEY#") "296-28183-1-ND")
        (field (name "MANF_1") "Texas Instruments")
        (field (name "MANF#_1") "TPS54260QDGQRQ1")
      )
      (libsource (lib "eagle-import") (part "TPS54260"))
    )
    (comp (ref "J1")
      (value "CONNECTION-7MM")
      (footprint "eagle-import:CONNECTION_7MM")
      (libsource (lib "eagle-import") (part "CONNECTION-7MM"))
    )
    (comp (ref "L1")
      (value "3.3uH")
      (footprint "eagle-import:IHLP-2020BZ-01")
      (fields (field (name "MANF") "Vishay Precision Group"))
      (libsource (lib "eagle-import") (part "3.3µH-IHLP-202BZ"))
    )
    (comp (ref "L2")
      (value "7.2uH")
      (footprint "eagle-import:1064")
      (fields (field (name "MANF") "Wurth Elektronik"))
      (libsource (lib "eagle-import") (part "7.2µH-1064"))
    )
    (comp (ref "L3")
      (value "22µH")
      (footprint "eagle-import:SRP1265A")
      (fields (field (name "MANF") "Bourns"))
      (libsource (lib "eagle-import") (part "22µH-SRP1265A"))
    )
    (comp (ref "L4")
      (value "7.2uH")
      (footprint "eagle-import:1064")
      (fields (field (name "MANF") "Wurth Elektronik"))
      (libsource (lib "eagle-import") (part "7.2µH-1064"))
    )
    (comp (ref "L5")
      (value "7.2uH")
      (footprint "eagle-import:1064")
      (fields (field (name "MANF") "Wurth Elektronik"))
      (libsource (lib "eagle-import") (part "7.2µH-1064"))
    )
    (comp (ref "R1")
      (value "243K")
      (footprint "eagle-import:R0603")
      (fields
        (field (name "PACKAGE") "0603")
        (field (name "TOLERANCE") "1%")
        (field (name "ALLOCATED") "+")
        (field (name "LCSC#") "C23351")
        (field (name "MANF") "UNI-ROYAL(Uniroyal Elec)")
        (field (name "MANF#") "0603WAF2433T5E")
      )
      (libsource (lib "eagle-import") (part "R-0603-1%"))
    )
    (comp (ref "R2")
      (value "18K")
      (footprint "eagle-import:R0603")
      (fields
        (field (name "PACKAGE") "0603")
        (field (name "TOLERANCE") "1%")
        (field (name "ALLOCATED") "+")
        (field (name "LCSC#") "C25810")
        (field (name "MANF") "UNI-ROYAL")
        (field (name "MANF#") "0603WAF1802T5E")
      )
      (libsource (lib "eagle-import") (part "R-0603-1%"))
    )
    (comp (ref "R3")
      (value "53K6")
      (footprint "eagle-import:R0603")
      (fields
        (field (name "PACKAGE") "0603")
        (field (name "TOLERANCE") "1%")
        (field (name "ALLOCATED") "+")
        (field (name "LCSC#") "C23074")
        (field (name "MANF") "UNI-ROYAL(Uniroyal Elec)")
        (field (name "MANF#") "0603WAF5362T5E")
      )
      (libsource (lib "eagle-import") (part "R-0603-1%"))
    )
    (comp (ref "R4")
      (value "10K")
      (footprint "eagle-import:R0603")
      (fields
        (field (name "PACKAGE") "0603")
        (field (name "TOLERANCE") "1%")
        (field (name "ALLOCATED") "+")
        (field (name "LCSC#") "C160601")
        (field (name "MANF") "YAGEO")
        (field (name "MANF#") "RT0603FRD0710KL")
      )
      (libsource (lib "eagle-import") (part "R-0603-1%"))
    )
    (comp (ref "R5")
      (value "243K")
      (footprint "eagle-import:R0603")
      (fields
        (field (name "PACKAGE") "0603")
        (field (name "TOLERANCE") "1%")
        (field (name "ALLOCATED") "+")
        (field (name "LCSC#") "C23351")
        (field (name "MANF") "UNI-ROYAL(Uniroyal Elec)")
        (field (name "MANF#") "0603WAF2433T5E")
      )
      (libsource (lib "eagle-import") (part "R-0603-1%"))
    )
    (comp (ref "R6")
      (value "18K")
      (footprint "eagle-import:R0603")
      (fields
        (field (name "PACKAGE") "0603")
        (field (name "TOLERANCE") "1%")
        (field (name "ALLOCATED") "+")
        (field (name "LCSC#") "C25810")
        (field (name "MANF") "UNI-ROYAL")
        (field (name "MANF#") "0603WAF1802T5E")
      )
      (libsource (lib "eagle-import") (part "R-0603-1%"))
    )
    (comp (ref "R7")
      (value "143K")
      (footprint "eagle-import:R0603")
      (fields
        (field (name "PACKAGE") "0603")
        (field (name "TOLERANCE") "1%")
        (field (name "ALLOCATED") "+")
        (field (name "LCSC#") "C22877")
        (field (name "MANF") "UNI-ROYAL(Uniroyal Elec)")
        (field (name "MANF#") "0603WAF1433T5E")
      )
      (libsource (lib "eagle-import") (part "R-0603-1%"))
    )
    (comp (ref "R8")
      (value "10K")
      (footprint "eagle-import:R0603")
      (fields
        (field (name "PACKAGE") "0603")
        (field (name "TOLERANCE") "1%")
        (field (name "ALLOCATED") "+")
        (field (name "LCSC#") "C160601")
        (field (name "MANF") "YAGEO")
        (field (name "MANF#") "RT0603FRD0710KL")
      )
      (libsource (lib "eagle-import") (part "R-0603-1%"))
    )
    (comp (ref "R9")
      (value "243K")
      (footprint "eagle-import:R0603")
      (fields
        (field (name "PACKAGE") "0603")
        (field (name "TOLERANCE") "1%")
        (field (name "ALLOCATED") "+")
        (field (name "LCSC#") "C23351")
        (field (name "MANF") "UNI-ROYAL(Uniroyal Elec)")
        (field (name "MANF#") "0603WAF2433T5E")
      )
      (libsource (lib "eagle-import") (part "R-0603-1%"))
    )
    (comp (ref "R10")
      (value "18K")
      (footprint "eagle-import:R0603")
      (fields
        (field (name "PACKAGE") "0603")
        (field (name "TOLERANCE") "1%")
        (field (name "ALLOCATED") "+")
        (field (name "LCSC#") "C25810")
        (field (name "MANF") "UNI-ROYAL")
        (field (name "MANF#") "0603WAF1802T5E")
      )
      (libsource (lib "eagle-import") (part "R-0603-1%"))
    )
    (comp (ref "R11")
      (value "53K6")
      (footprint "eagle-import:R0603")
      (fields
        (field (name "PACKAGE") "0603")
        (field (name "TOLERANCE") "1%")
        (field (name "ALLOCATED") "+")
        (field (name "LCSC#") "C23074")
        (field (name "MANF") "UNI-ROYAL(Uniroyal Elec)")
        (field (name "MANF#") "0603WAF5362T5E")
      )
      (libsource (lib "eagle-import") (part "R-0603-1%"))
    )
    (comp (ref "R12")
      (value "10K")
      (footprint "eagle-import:R0603")
      (fields
        (field (name "PACKAGE") "0603")
        (field (name "TOLERANCE") "1%")
        (field (name "ALLOCATED") "+")
        (field (name "LCSC#") "C160601")
        (field (name "MANF") "YAGEO")
        (field (name "MANF#") "RT0603FRD0710KL")
      )
      (libsource (lib "eagle-import") (part "R-0603-1%"))
    )
    (comp (ref "R13")
      (value "243K")
      (footprint "eagle-import:R0603")
      (fields
        (field (name "PACKAGE") "0603")
        (field (name "TOLERANCE") "1%")
        (field (name "ALLOCATED") "+")
        (field (name "LCSC#") "C23351")
        (field (name "MANF") "UNI-ROYAL(Uniroyal Elec)")
        (field (name "MANF#") "0603WAF2433T5E")
      )
      (libsource (lib "eagle-import") (part "R-0603-1%"))
    )
    (comp (ref "R14")
      (value "18K")
      (footprint "eagle-import:R0603")
      (fields
        (field (name "PACKAGE") "0603")
        (field (name "TOLERANCE") "1%")
        (field (name "ALLOCATED") "+")
        (field (name "LCSC#") "C25810")
        (field (name "MANF") "UNI-ROYAL")
        (field (name "MANF#") "0603WAF1802T5E")
      )
      (libsource (lib "eagle-import") (part "R-0603-1%"))
    )
    (comp (ref "R15")
      (value "143K")
      (footprint "eagle-import:R0603")
      (fields
        (field (name "PACKAGE") "0603")
        (field (name "TOLERANCE") "1%")
        (field (name "ALLOCATED") "+")
        (field (name "LCSC#") "C23074")
        (field (name "MANF") "UNI-ROYAL(Uniroyal Elec)")
        (field (name "MANF#") "0603WAF5362T5E")
      )
      (libsource (lib "eagle-import") (part "R-0603-1%"))
    )
    (comp (ref "R16")
      (value "10K")
      (footprint "eagle-import:R0603")
      (fields
        (field (name "PACKAGE") "0603")
        (field (name "TOLERANCE") "1%")
        (field (name "ALLOCATED") "+")
        (field (name "LCSC#") "C160601")
        (field (name "MANF") "YAGEO")
        (field (name "MANF#") "RT0603FRD0710KL")
      )
      (libsource (lib "eagle-import") (part "R-0603-1%"))
    )
    (comp (ref "R17")
      (value "10K")
      (footprint "eagle-import:R0603")
      (fields
        (field (name "PACKAGE") "0603")
        (field (name "TOLERANCE") "1%")
        (field (name "ALLOCATED") "+")
        (field (name "LCSC#") "C160601")
        (field (name "MANF") "YAGEO")
        (field (name "MANF#") "RT0603FRD0710KL")
      )
      (libsource (lib "eagle-import") (part "R-0603-1%"))
    )
    (comp (ref "R25")
      (value "143K")
      (footprint "eagle-import:R0603")
      (fields
        (field (name "PACKAGE") "0603")
        (field (name "TOLERANCE") "1%")
        (field (name "ALLOCATED") "+")
        (field (name "LCSC#") "C22877")
        (field (name "MANF") "UNI-ROYAL(Uniroyal Elec)")
        (field (name "MANF#") "0603WAF1433T5E")
      )
      (libsource (lib "eagle-import") (part "R-0603-1%"))
    )
    (comp (ref "R27")
      (value "143K")
      (footprint "eagle-import:R0603")
      (fields
        (field (name "PACKAGE") "0603")
        (field (name "TOLERANCE") "1%")
        (field (name "ALLOCATED") "+")
        (field (name "LCSC#") "C22877")
        (field (name "MANF") "UNI-ROYAL(Uniroyal Elec)")
        (field (name "MANF#") "0603WAF1433T5E")
      )
      (libsource (lib "eagle-import") (part "R-0603-1%"))
    )
    (comp (ref "R28")
      (value "10K")
      (footprint "eagle-import:R0603")
      (fields
        (field (name "PACKAGE") "0603")
        (field (name "TOLERANCE") "1%")
        (field (name "ALLOCATED") "+")
        (field (name "LCSC#") "C160601")
        (field (name "MANF") "YAGEO")
        (field (name "MANF#") "RT0603FRD0710KL")
      )
      (libsource (lib "eagle-import") (part "R-0603-1%"))
    )
    (comp (ref "R29")
      (value "18K")
      (footprint "eagle-import:R0603")
      (fields
        (field (name "PACKAGE") "0603")
        (field (name "TOLERANCE") "1%")
        (field (name "ALLOCATED") "+")
        (field (name "LCSC#") "C25810")
        (field (name "MANF") "UNI-ROYAL")
        (field (name "MANF#") "0603WAF1802T5E")
      )
      (libsource (lib "eagle-import") (part "R-0603-1%"))
    )
  )
  (nets
    (net (code "1") (name "5V") (class "Default")
      (node (ref "C22") (pin "P$2") (pinfunction "2_P$2") (pintype "passive"))
      (node (ref "C23") (pin "P$2") (pinfunction "2_P$2") (pintype "passive"))
      (node (ref "C24") (pin "P$2") (pinfunction "2_P$2") (pintype "passive"))
      (node (ref "CON4") (pin "1") (pinfunction "1_1") (pintype "passive"))
      (node (ref "CON4") (pin "2") (pinfunction "2_2") (pintype "passive"))
      (node (ref "CON4") (pin "3") (pinfunction "3_3") (pintype "passive"))
      (node (ref "L4") (pin "2") (pinfunction "2_2") (pintype "bidirectional"))
      (node (ref "R11") (pin "2") (pinfunction "2_2") (pintype "passive"))
    )
    (net (code "2") (name "5VFMU") (class "Default")
      (node (ref "C39") (pin "2") (pinfunction "2_2") (pintype "passive"))
      (node (ref "C7") (pin "P$2") (pinfunction "2_P$2") (pintype "passive"))
      (node (ref "C8") (pin "P$2") (pinfunction "2_P$2") (pintype "passive"))
      (node (ref "C9") (pin "P$2") (pinfunction "2_P$2") (pintype "passive"))
      (node (ref "CON1") (pin "10") (pinfunction "10_10") (pintype "passive"))
      (node (ref "CON1") (pin "8") (pinfunction "8_8") (pintype "passive"))
      (node (ref "CON1") (pin "9") (pinfunction "9_9") (pintype "passive"))
      (node (ref "IC5") (pin "5") (pinfunction "V+_5") (pintype "bidirectional"))
      (node (ref "L2") (pin "2") (pinfunction "2_2") (pintype "bidirectional"))
      (node (ref "R3") (pin "2") (pinfunction "2_2") (pintype "passive"))
    )
    (net (code "3") (name "12V") (class "Default")
      (node (ref "C36") (pin "P$2") (pinfunction "2_P$2") (pintype "passive"))
      (node (ref "C37") (pin "P$2") (pinfunction "2_P$2") (pintype "passive"))
      (node (ref "C38") (pin "P$2") (pinfunction "2_P$2") (pintype "passive"))
      (node (ref "CON7") (pin "1") (pinfunction "1_1") (pintype "passive"))
      (node (ref "CON7") (pin "2") (pinfunction "2_2") (pintype "passive"))
      (node (ref "CON7") (pin "3") (pinfunction "3_3") (pintype "passive"))
      (node (ref "L5") (pin "2") (pinfunction "2_2") (pintype "bidirectional"))
      (node (ref "R15") (pin "2") (pinfunction "2_2") (pintype "passive"))
    )
    (net (code "4") (name "24V") (class "Default")
      (node (ref "C28") (pin "2") (pinfunction "2_2") (pintype "passive"))
      (node (ref "C29") (pin "2") (pinfunction "2_2") (pintype "passive"))
      (node (ref "C30") (pin "2") (pinfunction "2_2") (pintype "passive"))
      (node (ref "C31") (pin "2") (pinfunction "2_2") (pintype "passive"))
      (node (ref "C32") (pin "2") (pinfunction "2_2") (pintype "passive"))
      (node (ref "C42") (pin "2") (pinfunction "2_2") (pintype "passive"))
      (node (ref "CON2") (pin "4") (pinfunction "4_4") (pintype "passive"))
      (node (ref "CON2") (pin "5") (pinfunction "5_5") (pintype "passive"))
      (node (ref "CON2") (pin "6") (pinfunction "6_6") (pintype "passive"))
      (node (ref "L3") (pin "2") (pinfunction "2_2") (pintype "bidirectional"))
      (node (ref "R7") (pin "2") (pinfunction "2_2") (pintype "passive"))
    )
    (net (code "5") (name "B1MID") (class "Default")
      (node (ref "B1H") (pin "-") (pinfunction "-_-") (pintype "bidirectional"))
      (node (ref "B1L") (pin "+") (pinfunction "+_+") (pintype "bidirectional"))
      (node (ref "PAD4") (pin "P$1") (pinfunction "P$1_P$1") (pintype "bidirectional"))
      (node (ref "PAD8") (pin "P$1") (pinfunction "P$1_P$1") (pintype "bidirectional"))
    )
    (net (code "6") (name "B2MID") (class "Default")
      (node (ref "B3H") (pin "-") (pinfunction "-_-") (pintype "bidirectional"))
      (node (ref "B3L") (pin "+") (pinfunction "+_+") (pintype "bidirectional"))
      (node (ref "PAD1") (pin "P$1") (pinfunction "P$1_P$1") (pintype "bidirectional"))
      (node (ref "PAD2") (pin "P$1") (pinfunction "P$1_P$1") (pintype "bidirectional"))
    )
    (net (code "7") (name "B3MID") (class "Default")
      (node (ref "B2H") (pin "-") (pinfunction "-_-") (pintype "bidirectional"))
      (node (ref "B2L") (pin "+") (pinfunction "+_+") (pintype "bidirectional"))
      (node (ref "PAD3") (pin "P$1") (pinfunction "P$1_P$1") (pintype "bidirectional"))
      (node (ref "PAD5") (pin "P$1") (pinfunction "P$1_P$1") (pintype "bidirectional"))
    )
    (net (code "8") (name "BATNEG") (class "Default")
      (node (ref "B1L") (pin "-") (pinfunction "-_-") (pintype "bidirectional"))
      (node (ref "B2L") (pin "-") (pinfunction "-_-") (pintype "bidirectional"))
      (node (ref "B3L") (pin "-") (pinfunction "-_-") (pintype "bidirectional"))
      (node (ref "CON3") (pin "1") (pinfunction "1_1") (pintype "passive"))
      (node (ref "D5") (pin "1") (pinfunction "A_1") (pintype "passive"))
      (node (ref "Q1") (pin "S") (pinfunction "S_S") (pintype "passive"))
      (node (ref "Q2") (pin "S") (pinfunction "S_S") (pintype "passive"))
      (node (ref "Q3") (pin "S") (pinfunction "S_S") (pintype "passive"))
      (node (ref "R24") (pin "2") (pinfunction "2_2") (pintype "passive"))
    )
    (net (code "9") (name "BATT_CURRENT") (class "Default")
      (node (ref "C40") (pin "2") (pinfunction "2_2") (pintype "passive"))
      (node (ref "CON1") (pin "12") (pinfunction "12_12") (pintype "passive"))
      (node (ref "IC5") (pin "1") (pinfunction "OUT_1") (pintype "bidirectional"))
      (node (ref "R19") (pin "2") (pinfunction "2_2") (pintype "passive"))
    )
    (net (code "10") (name "BATT_VOLTAGE") (class "Default")
      (node (ref "C41") (pin "2") (pinfunction "2_2") (pintype "passive"))
      (node (ref "CON1") (pin "11") (pinfunction "11_11") (pintype "passive"))
      (node (ref "R20") (pin "2") (pinfunction "2_2") (pintype "passive"))
      (node (ref "R22") (pin "1") (pinfunction "1_1") (pintype "passive"))
    )
    (net (code "11") (name "GND") (class "Default")
      (node (ref "C11") (pin "P$1") (pinfunction "1_P$1") (pintype "passive"))
      (node (ref "C12") (pin "P$1") (pinfunction "1_P$1") (pintype "passive"))
      (node (ref "C13") (pin "P$1") (pinfunction "1_P$1") (pintype "passive"))
      (node (ref "C14") (pin "1") (pinfunction "1_1") (pintype "passive"))
      (node (ref "C15") (pin "1") (pinfunction "1_1") (pintype "passive"))
      (node (ref "C17") (pin "P$1") (pinfunction "1_P$1") (pintype "passive"))
      (node (ref "C18") (pin "P$1") (pinfunction "1_P$1") (pintype "passive"))
      (node (ref "C19") (pin "P$1") (pinfunction "1_P$1") (pintype "passive"))
      (node (ref "C2") (pin "P$1") (pinfunction "1_P$1") (pintype "passive"))
      (node (ref "C20") (pin "1") (pinfunction "1_1") (pintype "passive"))
      (node (ref "C21") (pin "1") (pinfunction "1_1") (pintype "passive"))
      (node (ref "C22") (pin "P$1") (pinfunction "1_P$1") (pintype "passive"))
      (node (ref "C23") (pin "P$1") (pinfunction "1_P$1") (pintype "passive"))
      (node (ref "C24") (pin "P$1") (pinfunction "1_P$1") (pintype "passive"))
      (node (ref "C26") (pin "P$1") (pinfunction "1_P$1") (pintype "passive"))
      (node (ref "C27") (pin "P$1") (pinfunction "1_P$1") (pintype "passive"))
      (node (ref "C28") (pin "1") (pinfunction "1_1") (pintype "passive"))
      (node (ref "C29") (pin "1") (pinfunction "1_1") (pintype "passive"))
      (node (ref "C3") (pin "P$1") (pinfunction "1_P$1") (pintype "passive"))
      (node (ref "C30") (pin "1") (pinfunction "1_1") (pintype "passive"))
      (node (ref "C31") (pin "1") (pinfunction "1_1") (pintype "passive"))
      (node (ref "C32") (pin "1") (pinfunction "1_1") (pintype "passive"))
      (node (ref "C33") (pin "P$1") (pinfunction "1_P$1") (pintype "passive"))
      (node (ref "C34") (pin "1") (pinfunction "1_1") (pintype "passive"))
      (node (ref "C35") (pin "1") (pinfunction "1_1") (pintype "passive"))
      (node (ref "C36") (pin "P$1") (pinfunction "1_P$1") (pintype "passive"))
      (node (ref "C37") (pin "P$1") (pinfunction "1_P$1") (pintype "passive"))
      (node (ref "C38") (pin "P$1") (pinfunction "1_P$1") (pintype "passive"))
      (node (ref "C39") (pin "1") (pinfunction "1_1") (pintype "passive"))
      (node (ref "C4") (pin "P$1") (pinfunction "1_P$1") (pintype "passive"))
      (node (ref "C40") (pin "1") (pinfunction "1_1") (pintype "passive"))
      (node (ref "C41") (pin "1") (pinfunction "1_1") (pintype "passive"))
      (node (ref "C42") (pin "1") (pinfunction "1_1") (pintype "passive"))
      (node (ref "C43") (pin "P$2") (pinfunction "2_P$2") (pintype "passive"))
      (node (ref "C44") (pin "P$1") (pinfunction "1_P$1") (pintype "passive"))
      (node (ref "C5") (pin "1") (pinfunction "1_1") (pintype "passive"))
      (node (ref "C54") (pin "P$1") (pinfunction "1_P$1") (pintype "passive"))
      (node (ref "C56") (pin "P$2") (pinfunction "2_P$2") (pintype "passive"))
      (node (ref "C57") (pin "P$2") (pinfunction "2_P$2") (pintype "passive"))
      (node (ref "C6") (pin "1") (pinfunction "1_1") (pintype "passive"))
      (node (ref "C62") (pin "2") (pinfunction "2_2") (pintype "passive"))
      (node (ref "C7") (pin "P$1") (pinfunction "1_P$1") (pintype "passive"))
      (node (ref "C8") (pin "P$1") (pinfunction "1_P$1") (pintype "passive"))
      (node (ref "C87") (pin "2") (pinfunction "2_2") (pintype "passive"))
      (node (ref "C88") (pin "2") (pinfunction "2_2") (pintype "passive"))
      (node (ref "C9") (pin "P$1") (pinfunction "1_P$1") (pintype "passive"))
      (node (ref "CON1") (pin "1") (pinfunction "1_1") (pintype "passive"))
      (node (ref "CON1") (pin "2") (pinfunction "2_2") (pintype "passive"))
      (node (ref "CON1") (pin "5") (pinfunction "5_5") (pintype "passive"))
      (node (ref "CON1") (pin "6") (pinfunction "6_6") (pintype "passive"))
      (node (ref "CON1") (pin "7") (pinfunction "7_7") (pintype "passive"))
      (node (ref "CON2") (pin "1") (pinfunction "1_1") (pintype "passive"))
      (node (ref "CON2") (pin "2") (pinfunction "2_2") (pintype "passive"))
      (node (ref "CON2") (pin "3") (pinfunction "3_3") (pintype "passive"))
      (node (ref "CON4") (pin "4") (pinfunction "4_4") (pintype "passive"))
      (node (ref "CON4") (pin "5") (pinfunction "5_5") (pintype "passive"))
      (node (ref "CON4") (pin "6") (pinfunction "6_6") (pintype "passive"))
      (node (ref "CON7") (pin "4") (pinfunction "4_4") (pintype "passive"))
      (node (ref "CON7") (pin "5") (pinfunction "5_5") (pintype "passive"))
      (node (ref "CON7") (pin "6") (pinfunction "6_6") (pintype "passive"))
      (node (ref "D1") (pin "A") (pinfunction "A_A") (pintype "passive"))
      (node (ref "D10") (pin "A") (pinfunction "A_A") (pintype "passive"))
      (node (ref "D2") (pin "A") (pinfunction "A_A") (pintype "passive"))
      (node (ref "D3") (pin "A") (pinfunction "A_A") (pintype "passive"))
      (node (ref "D4") (pin "A") (pinfunction "A_A") (pintype "passive"))
      (node (ref "IC1") (pin "7") (pinfunction "GND_7") (pintype "bidirectional"))
      (node (ref "IC1") (pin "P$1") (pinfunction "GND_P$1") (pintype "bidirectional"))
      (node (ref "IC10") (pin "9") (pinfunction "GND_9") (pintype "bidirectional"))
      (node (ref "IC10") (pin "EP") (pinfunction "GND_EP") (pintype "bidirectional"))
      (node (ref "IC2") (pin "7") (pinfunction "GND_7") (pintype "bidirectional"))
      (node (ref "IC2") (pin "P$1") (pinfunction "GND_P$1") (pintype "bidirectional"))
      (node (ref "IC3") (pin "7") (pinfunction "GND_7") (pintype "bidirectional"))
      (node (ref "IC3") (pin "P$1") (pinfunction "GND_P$1") (pintype "bidirectional"))
      (node (ref "IC4") (pin "7") (pinfunction "GND_7") (pintype "bidirectional"))
      (node (ref "IC4") (pin "P$1") (pinfunction "GND_P$1") (pintype "bidirectional"))
      (node (ref "IC5") (pin "2") (pinfunction "GND_2") (pintype "bidirectional"))
      (node (ref "J1") (pin "2") (pinfunction "P$2_2") (pintype "bidirectional"))
      (node (ref "R1") (pin "1") (pinfunction "1_1") (pintype "passive"))
      (node (ref "R12") (pin "1") (pinfunction "1_1") (pintype "passive"))
      (node (ref "R13") (pin "1") (pinfunction "1_1") (pintype "passive"))
      (node (ref "R16") (pin "1") (pinfunction "1_1") (pintype "passive"))
      (node (ref "R17") (pin "1") (pinfunction "1_1") (pintype "passive"))
      (node (ref "R19") (pin "1") (pinfunction "1_1") (pintype "passive"))
      (node (ref "R20") (pin "1") (pinfunction "1_1") (pintype "passive"))
      (node (ref "R25") (pin "1") (pinfunction "1_1") (pintype "passive"))
      (node (ref "R28") (pin "1") (pinfunction "1_1") (pintype "passive"))
      (node (ref "R4") (pin "1") (pinfunction "1_1") (pintype "passive"))
      (node (ref "R5") (pin "1") (pinfunction "1_1") (pintype "passive"))
      (node (ref "R8") (pin "1") (pinfunction "1_1") (pintype "passive"))
      (node (ref "R9") (pin "1") (pinfunction "1_1") (pintype "passive"))
    )
    (net (code "12") (name "Net-(C5-Pad2)") (class "Default")
      (node (ref "C5") (pin "2") (pinfunction "2_2") (pintype "passive"))
      (node (ref "R2") (pin "1") (pinfunction "1_1") (pintype "passive"))
    )
    (net (code "13") (name "Net-(C14-Pad2)") (class "Default")
      (node (ref "C14") (pin "2") (pinfunction "2_2") (pintype "passive"))
      (node (ref "R6") (pin "1") (pinfunction "1_1") (pintype "passive"))
    )
    (net (code "14") (name "Net-(C20-Pad2)") (class "Default")
      (node (ref "C20") (pin "2") (pinfunction "2_2") (pintype "passive"))
      (node (ref "R10") (pin "1") (pinfunction "1_1") (pintype "passive"))
    )
    (net (code "15") (name "Net-(C34-Pad2)") (class "Default")
      (node (ref "C34") (pin "2") (pinfunction "2_2") (pintype "passive"))
      (node (ref "R14") (pin "1") (pinfunction "1_1") (pintype "passive"))
    )
    (net (code "16") (name "Net-(C88-Pad1)") (class "Default")
      (node (ref "C88") (pin "1") (pinfunction "1_1") (pintype "passive"))
      (node (ref "R29") (pin "1") (pinfunction "1_1") (pintype "passive"))
    )
    (net (code "17") (name "Net-(IC1-BOOT)") (class "Default")
      (node (ref "C1") (pin "1") (pinfunction "1_1") (pintype "passive"))
      (node (ref "IC1") (pin "1") (pinfunction "BOOT_1") (pintype "bidirectional"))
    )
    (net (code "18") (name "Net-(IC1-COMP)") (class "Default")
      (node (ref "C6") (pin "2") (pinfunction "2_2") (pintype "passive"))
      (node (ref "IC1") (pin "6") (pinfunction "COMP_6") (pintype "bidirectional"))
      (node (ref "R2") (pin "2") (pinfunction "2_2") (pintype "passive"))
    )
    (net (code "19") (name "Net-(IC1-FB)") (class "Default")
      (node (ref "IC1") (pin "5") (pinfunction "FB_5") (pintype "bidirectional"))
      (node (ref "R3") (pin "1") (pinfunction "1_1") (pintype "passive"))
      (node (ref "R4") (pin "2") (pinfunction "2_2") (pintype "passive"))
    )
    (net (code "20") (name "Net-(IC1-RT{slash}CLK)") (class "Default")
      (node (ref "IC1") (pin "4") (pinfunction "RT/CLK_4") (pintype "bidirectional"))
      (node (ref "R1") (pin "2") (pinfunction "2_2") (pintype "passive"))
    )
    (net (code "21") (name "Net-(IC1-SW)") (class "Default")
      (node (ref "C1") (pin "2") (pinfunction "2_2") (pintype "passive"))
      (node (ref "D1") (pin "C") (pinfunction "C_C") (pintype "passive"))
      (node (ref "IC1") (pin "8") (pinfunction "SW_8") (pintype "bidirectional"))
      (node (ref "L2") (pin "1") (pinfunction "1_1") (pintype "bidirectional"))
    )
    (net (code "22") (name "Net-(IC2-BOOT)") (class "Default")
      (node (ref "C10") (pin "1") (pinfunction "1_1") (pintype "passive"))
      (node (ref "IC2") (pin "1") (pinfunction "BOOT_1") (pintype "bidirectional"))
    )
    (net (code "23") (name "Net-(IC2-COMP)") (class "Default")
      (node (ref "C15") (pin "2") (pinfunction "2_2") (pintype "passive"))
      (node (ref "IC2") (pin "6") (pinfunction "COMP_6") (pintype "bidirectional"))
      (node (ref "R6") (pin "2") (pinfunction "2_2") (pintype "passive"))
    )
    (net (code "24") (name "Net-(IC2-FB)") (class "Default")
      (node (ref "IC2") (pin "5") (pinfunction "FB_5") (pintype "bidirectional"))
      (node (ref "R17") (pin "2") (pinfunction "2_2") (pintype "passive"))
      (node (ref "R7") (pin "1") (pinfunction "1_1") (pintype "passive"))
      (node (ref "R8") (pin "2") (pinfunction "2_2") (pintype "passive"))
    )
    (net (code "25") (name "Net-(IC2-RT{slash}CLK)") (class "Default")
      (node (ref "IC2") (pin "4") (pinfunction "RT/CLK_4") (pintype "bidirectional"))
      (node (ref "R5") (pin "2") (pinfunction "2_2") (pintype "passive"))
    )
    (net (code "26") (name "Net-(IC2-SW)") (class "Default")
      (node (ref "C10") (pin "2") (pinfunction "2_2") (pintype "passive"))
      (node (ref "D2") (pin "C") (pinfunction "C_C") (pintype "passive"))
      (node (ref "IC2") (pin "8") (pinfunction "SW_8") (pintype "bidirectional"))
      (node (ref "L3") (pin "1") (pinfunction "1_1") (pintype "bidirectional"))
    )
    (net (code "27") (name "Net-(IC3-BOOT)") (class "Default")
      (node (ref "C16") (pin "1") (pinfunction "1_1") (pintype "passive"))
      (node (ref "IC3") (pin "1") (pinfunction "BOOT_1") (pintype "bidirectional"))
    )
    (net (code "28") (name "Net-(IC3-COMP)") (class "Default")
      (node (ref "C21") (pin "2") (pinfunction "2_2") (pintype "passive"))
      (node (ref "IC3") (pin "6") (pinfunction "COMP_6") (pintype "bidirectional"))
      (node (ref "R10") (pin "2") (pinfunction "2_2") (pintype "passive"))
    )
    (net (code "29") (name "Net-(IC3-FB)") (class "Default")
      (node (ref "IC3") (pin "5") (pinfunction "FB_5") (pintype "bidirectional"))
      (node (ref "R11") (pin "1") (pinfunction "1_1") (pintype "passive"))
      (node (ref "R12") (pin "2") (pinfunction "2_2") (pintype "passive"))
    )
    (net (code "30") (name "Net-(IC3-RT{slash}CLK)") (class "Default")
      (node (ref "IC3") (pin "4") (pinfunction "RT/CLK_4") (pintype "bidirectional"))
      (node (ref "R9") (pin "2") (pinfunction "2_2") (pintype "passive"))
    )
    (net (code "31") (name "Net-(IC3-SW)") (class "Default")
      (node (ref "C16") (pin "2") (pinfunction "2_2") (pintype "passive"))
      (node (ref "D3") (pin "C") (pinfunction "C_C") (pintype "passive"))
      (node (ref "IC3") (pin "8") (pinfunction "SW_8") (pintype "bidirectional"))
      (node (ref "L4") (pin "1") (pinfunction "1_1") (pintype "bidirectional"))
    )
    (net (code "32") (name "Net-(IC4-BOOT)") (class "Default")
      (node (ref "C25") (pin "1") (pinfunction "1_1") (pintype "passive"))
      (node (ref "IC4") (pin "1") (pinfunction "BOOT_1") (pintype "bidirectional"))
    )
    (net (code "33") (name "Net-(IC4-COMP)") (class "Default")
      (node (ref "C35") (pin "2") (pinfunction "2_2") (pintype "passive"))
      (node (ref "IC4") (pin "6") (pinfunction "COMP_6") (pintype "bidirectional"))
      (node (ref "R14") (pin "2") (pinfunction "2_2") (pintype "passive"))
    )
    (net (code "34") (name "Net-(IC4-FB)") (class "Default")
      (node (ref "IC4") (pin "5") (pinfunction "FB_5") (pintype "bidirectional"))
      (node (ref "R15") (pin "1") (pinfunction "1_1") (pintype "passive"))
      (node (ref "R16") (pin "2") (pinfunction "2_2") (pintype "passive"))
    )
    (net (code "35") (name "Net-(IC4-RT{slash}CLK)") (class "Default")
      (node (ref "IC4") (pin "4") (pinfunction "RT/CLK_4") (pintype "bidirectional"))
      (node (ref "R13") (pin "2") (pinfunction "2_2") (pintype "passive"))
    )
    (net (code "36") (name "Net-(IC4-SW)") (class "Default")
      (node (ref "C25") (pin "2") (pinfunction "2_2") (pintype "passive"))
      (node (ref "D4") (pin "C") (pinfunction "C_C") (pintype "passive"))
      (node (ref "IC4") (pin "8") (pinfunction "SW_8") (pintype "bidirectional"))
      (node (ref "L5") (pin "1") (pinfunction "1_1") (pintype "bidirectional"))
    )
    (net (code "37") (name "Net-(IC5-VIN+)") (class "Default")
      (node (ref "IC5") (pin "3") (pinfunction "VIN+_3") (pintype "bidirectional"))
      (node (ref "R18") (pin "S1") (pinfunction "S1_S1") (pintype "bidirectional"))
    )
    (net (code "38") (name "Net-(IC5-VIN-)") (class "Default")
      (node (ref "IC5") (pin "4") (pinfunction "VIN-_4") (pintype "bidirectional"))
      (node (ref "R18") (pin "S2") (pinfunction "S2_S2") (pintype "bidirectional"))
    )
    (net (code "39") (name "Net-(IC10-BOOT)") (class "Default")
      (node (ref "C58") (pin "2") (pinfunction "2_2") (pintype "passive"))
      (node (ref "IC10") (pin "1") (pinfunction "BOOT_1") (pintype "bidirectional"))
    )
    (net (code "40") (name "Net-(IC10-COMP)") (class "Default")
      (node (ref "C87") (pin "1") (pinfunction "1_1") (pintype "passive"))
      (node (ref "IC10") (pin "8") (pinfunction "COMP_8") (pintype "bidirectional"))
      (node (ref "R29") (pin "2") (pinfunction "2_2") (pintype "passive"))
    )
    (net (code "41") (name "Net-(IC10-PH)") (class "Default")
      (node (ref "C58") (pin "1") (pinfunction "1_1") (pintype "passive"))
      (node (ref "D10") (pin "C") (pinfunction "C_C") (pintype "passive"))
      (node (ref "IC10") (pin "10") (pinfunction "PH_10") (pintype "bidirectional"))
      (node (ref "L1") (pin "P$1") (pinfunction "1_P$1") (pintype "bidirectional"))
    )
    (net (code "42") (name "Net-(IC10-RT{slash}CLK)") (class "Default")
      (node (ref "IC10") (pin "5") (pinfunction "RT/CLK_5") (pintype "bidirectional"))
      (node (ref "R25") (pin "2") (pinfunction "2_2") (pintype "passive"))
    )
    (net (code "43") (name "Net-(IC10-SS{slash}TR)") (class "Default")
      (node (ref "C62") (pin "1") (pinfunction "1_1") (pintype "passive"))
      (node (ref "IC10") (pin "4") (pinfunction "SS/TR_4") (pintype "bidirectional"))
    )
    (net (code "44") (name "Net-(IC10-VSENSE)") (class "Default")
      (node (ref "IC10") (pin "7") (pinfunction "VSENSE_7") (pintype "bidirectional"))
      (node (ref "R27") (pin "1") (pinfunction "1_1") (pintype "passive"))
      (node (ref "R28") (pin "2") (pinfunction "2_2") (pintype "passive"))
    )
    (net (code "45") (name "Net-(R21-Pad1)") (class "Default")
      (node (ref "R21") (pin "1") (pinfunction "1_1") (pintype "passive"))
      (node (ref "R22") (pin "2") (pinfunction "2_2") (pintype "passive"))
    )
    (net (code "46") (name "PGND") (class "Default")
      (node (ref "J1") (pin "1") (pinfunction "P$1_1") (pintype "bidirectional"))
      (node (ref "M1") (pin "-") (pinfunction "-_-") (pintype "bidirectional"))
      (node (ref "M2") (pin "-") (pinfunction "-_-") (pintype "bidirectional"))
      (node (ref "M3") (pin "-") (pinfunction "-_-") (pintype "bidirectional"))
      (node (ref "M4") (pin "-") (pinfunction "-_-") (pintype "bidirectional"))
      (node (ref "M5") (pin "-") (pinfunction "-_-") (pintype "bidirectional"))
      (node (ref "M6") (pin "-") (pinfunction "-_-") (pintype "bidirectional"))
      (node (ref "M7") (pin "-") (pinfunction "-_-") (pintype "bidirectional"))
      (node (ref "Q1") (pin "D") (pinfunction "D_D") (pintype "passive"))
      (node (ref "Q2") (pin "D") (pinfunction "D_D") (pintype "passive"))
      (node (ref "Q3") (pin "D") (pinfunction "D_D") (pintype "passive"))
    )
    (net (code "47") (name "PWRSW") (class "Default")
      (node (ref "CON3") (pin "2") (pinfunction "2_2") (pintype "passive"))
      (node (ref "D5") (pin "3") (pinfunction "C_3") (pintype "passive"))
      (node (ref "Q1") (pin "G") (pinfunction "G_G") (pintype "passive"))
      (node (ref "Q2") (pin "G") (pinfunction "G_G") (pintype "passive"))
      (node (ref "Q3") (pin "G") (pinfunction "G_G") (pintype "passive"))
      (node (ref "R23") (pin "2") (pinfunction "2_2") (pintype "passive"))
      (node (ref "R24") (pin "1") (pinfunction "1_1") (pintype "passive"))
    )
    (net (code "48") (name "VBAT") (class "Default")
      (node (ref "C11") (pin "P$2") (pinfunction "2_P$2") (pintype "passive"))
      (node (ref "C12") (pin "P$2") (pinfunction "2_P$2") (pintype "passive"))
      (node (ref "C13") (pin "P$2") (pinfunction "2_P$2") (pintype "passive"))
      (node (ref "C17") (pin "P$2") (pinfunction "2_P$2") (pintype "passive"))
      (node (ref "C18") (pin "P$2") (pinfunction "2_P$2") (pintype "passive"))
      (node (ref "C19") (pin "P$2") (pinfunction "2_P$2") (pintype "passive"))
      (node (ref "C2") (pin "P$2") (pinfunction "2_P$2") (pintype "passive"))
      (node (ref "C26") (pin "P$2") (pinfunction "2_P$2") (pintype "passive"))
      (node (ref "C27") (pin "P$2") (pinfunction "2_P$2") (pintype "passive"))
      (node (ref "C3") (pin "P$2") (pinfunction "2_P$2") (pintype "passive"))
      (node (ref "C33") (pin "P$2") (pinfunction "2_P$2") (pintype "passive"))
      (node (ref "C4") (pin "P$2") (pinfunction "2_P$2") (pintype "passive"))
      (node (ref "C44") (pin "P$2") (pinfunction "2_P$2") (pintype "passive"))
      (node (ref "C54") (pin "P$2") (pinfunction "2_P$2") (pintype "passive"))
      (node (ref "IC1") (pin "2") (pinfunction "VIN_2") (pintype "bidirectional"))
      (node (ref "IC10") (pin "2") (pinfunction "VIN_2") (pintype "bidirectional"))
      (node (ref "IC2") (pin "2") (pinfunction "VIN_2") (pintype "bidirectional"))
      (node (ref "IC3") (pin "2") (pinfunction "VIN_2") (pintype "bidirectional"))
      (node (ref "IC4") (pin "2") (pinfunction "VIN_2") (pintype "bidirectional"))
      (node (ref "M1") (pin "+") (pinfunction "+_+") (pintype "bidirectional"))
      (node (ref "M2") (pin "+") (pinfunction "+_+") (pintype "bidirectional"))
      (node (ref "M3") (pin "+") (pinfunction "+_+") (pintype "bidirectional"))
      (node (ref "M4") (pin "+") (pinfunction "+_+") (pintype "bidirectional"))
      (node (ref "M5") (pin "+") (pinfunction "+_+") (pintype "bidirectional"))
      (node (ref "M6") (pin "+") (pinfunction "+_+") (pintype "bidirectional"))
      (node (ref "M7") (pin "+") (pinfunction "+_+") (pintype "bidirectional"))
      (node (ref "R18") (pin "2") (pinfunction "2_2") (pintype "bidirectional"))
      (node (ref "R18") (pin "22") (pinfunction "2_22") (pintype "bidirectional"))
      (node (ref "R21") (pin "2") (pinfunction "2_2") (pintype "passive"))
      (node (ref "R23") (pin "1") (pinfunction "1_1") (pintype "passive"))
    )
    (net (code "49") (name "VDC") (class "Default")
      (node (ref "B1H") (pin "+") (pinfunction "+_+") (pintype "bidirectional"))
      (node (ref "B2H") (pin "+") (pinfunction "+_+") (pintype "bidirectional"))
      (node (ref "B3H") (pin "+") (pinfunction "+_+") (pintype "bidirectional"))
      (node (ref "R18") (pin "1") (pinfunction "1_1") (pintype "bidirectional"))
      (node (ref "R18") (pin "11") (pinfunction "1_11") (pintype "bidirectional"))
    )
    (net (code "50") (name "VDD_4V") (class "Default")
      (node (ref "C43") (pin "P$1") (pinfunction "1_P$1") (pintype "passive"))
      (node (ref "C56") (pin "P$1") (pinfunction "1_P$1") (pintype "passive"))
      (node (ref "C57") (pin "P$1") (pinfunction "1_P$1") (pintype "passive"))
      (node (ref "CON1") (pin "3") (pinfunction "3_3") (pintype "passive"))
      (node (ref "CON1") (pin "4") (pinfunction "4_4") (pintype "passive"))
      (node (ref "L1") (pin "P$2") (pinfunction "2_P$2") (pintype "bidirectional"))
      (node (ref "R27") (pin "2") (pinfunction "2_2") (pintype "passive"))
    )
    (net (code "51") (name "unconnected-(B1H-PAD1-PadP$3)") (class "Default")
      (node (ref "B1H") (pin "P$3") (pinfunction "PAD1_P$3") (pintype "bidirectional"))
    )
    (net (code "52") (name "unconnected-(B1H-PAD2-PadP$4)") (class "Default")
      (node (ref "B1H") (pin "P$4") (pinfunction "PAD2_P$4") (pintype "bidirectional"))
    )
    (net (code "53") (name "unconnected-(B1L-PAD1-PadP$3)") (class "Default")
      (node (ref "B1L") (pin "P$3") (pinfunction "PAD1_P$3") (pintype "bidirectional"))
    )
    (net (code "54") (name "unconnected-(B1L-PAD2-PadP$4)") (class "Default")
      (node (ref "B1L") (pin "P$4") (pinfunction "PAD2_P$4") (pintype "bidirectional"))
    )
    (net (code "55") (name "unconnected-(B2H-PAD1-PadP$3)") (class "Default")
      (node (ref "B2H") (pin "P$3") (pinfunction "PAD1_P$3") (pintype "bidirectional"))
    )
    (net (code "56") (name "unconnected-(B2H-PAD2-PadP$4)") (class "Default")
      (node (ref "B2H") (pin "P$4") (pinfunction "PAD2_P$4") (pintype "bidirectional"))
    )
    (net (code "57") (name "unconnected-(B2L-PAD1-PadP$3)") (class "Default")
      (node (ref "B2L") (pin "P$3") (pinfunction "PAD1_P$3") (pintype "bidirectional"))
    )
    (net (code "58") (name "unconnected-(B2L-PAD2-PadP$4)") (class "Default")
      (node (ref "B2L") (pin "P$4") (pinfunction "PAD2_P$4") (pintype "bidirectional"))
    )
    (net (code "59") (name "unconnected-(B3H-PAD1-PadP$3)") (class "Default")
      (node (ref "B3H") (pin "P$3") (pinfunction "PAD1_P$3") (pintype "bidirectional"))
    )
    (net (code "60") (name "unconnected-(B3H-PAD2-PadP$4)") (class "Default")
      (node (ref "B3H") (pin "P$4") (pinfunction "PAD2_P$4") (pintype "bidirectional"))
    )
    (net (code "61") (name "unconnected-(B3L-PAD1-PadP$3)") (class "Default")
      (node (ref "B3L") (pin "P$3") (pinfunction "PAD1_P$3") (pintype "bidirectional"))
    )
    (net (code "62") (name "unconnected-(B3L-PAD2-PadP$4)") (class "Default")
      (node (ref "B3L") (pin "P$4") (pinfunction "PAD2_P$4") (pintype "bidirectional"))
    )
    (net (code "63") (name "unconnected-(IC1-EN-Pad3)") (class "Default")
      (node (ref "IC1") (pin "3") (pinfunction "EN_3") (pintype "bidirectional"))
    )
    (net (code "64") (name "unconnected-(IC2-EN-Pad3)") (class "Default")
      (node (ref "IC2") (pin "3") (pinfunction "EN_3") (pintype "bidirectional"))
    )
    (net (code "65") (name "unconnected-(IC3-EN-Pad3)") (class "Default")
      (node (ref "IC3") (pin "3") (pinfunction "EN_3") (pintype "bidirectional"))
    )
    (net (code "66") (name "unconnected-(IC4-EN-Pad3)") (class "Default")
      (node (ref "IC4") (pin "3") (pinfunction "EN_3") (pintype "bidirectional"))
    )
    (net (code "67") (name "unconnected-(IC10-EN-Pad3)") (class "Default")
      (node (ref "IC10") (pin "3") (pinfunction "EN_3") (pintype "bidirectional"))
    )
    (net (code "68") (name "unconnected-(IC10-PWRGD-Pad6)") (class "Default")
      (node (ref "IC10") (pin "6") (pinfunction "PWRGD_6") (pintype "bidirectional"))
    )
    (net (code "69") (name "unconnected-(M1-PAD1-PadP$3)") (class "Default")
      (node (ref "M1") (pin "P$3") (pinfunction "PAD1_P$3") (pintype "bidirectional"))
    )
    (net (code "70") (name "unconnected-(M1-PAD2-PadP$4)") (class "Default")
      (node (ref "M1") (pin "P$4") (pinfunction "PAD2_P$4") (pintype "bidirectional"))
    )
    (net (code "71") (name "unconnected-(M2-PAD1-PadP$3)") (class "Default")
      (node (ref "M2") (pin "P$3") (pinfunction "PAD1_P$3") (pintype "bidirectional"))
    )
    (net (code "72") (name "unconnected-(M2-PAD2-PadP$4)") (class "Default")
      (node (ref "M2") (pin "P$4") (pinfunction "PAD2_P$4") (pintype "bidirectional"))
    )
    (net (code "73") (name "unconnected-(M3-PAD1-PadP$3)") (class "Default")
      (node (ref "M3") (pin "P$3") (pinfunction "PAD1_P$3") (pintype "bidirectional"))
    )
    (net (code "74") (name "unconnected-(M3-PAD2-PadP$4)") (class "Default")
      (node (ref "M3") (pin "P$4") (pinfunction "PAD2_P$4") (pintype "bidirectional"))
    )
    (net (code "75") (name "unconnected-(M4-PAD1-PadP$3)") (class "Default")
      (node (ref "M4") (pin "P$3") (pinfunction "PAD1_P$3") (pintype "bidirectional"))
    )
    (net (code "76") (name "unconnected-(M4-PAD2-PadP$4)") (class "Default")
      (node (ref "M4") (pin "P$4") (pinfunction "PAD2_P$4") (pintype "bidirectional"))
    )
    (net (code "77") (name "unconnected-(M5-PAD1-PadP$3)") (class "Default")
      (node (ref "M5") (pin "P$3") (pinfunction "PAD1_P$3") (pintype "bidirectional"))
    )
    (net (code "78") (name "unconnected-(M5-PAD2-PadP$4)") (class "Default")
      (node (ref "M5") (pin "P$4") (pinfunction "PAD2_P$4") (pintype "bidirectional"))
    )
    (net (code "79") (name "unconnected-(M6-PAD1-PadP$3)") (class "Default")
      (node (ref "M6") (pin "P$3") (pinfunction "PAD1_P$3") (pintype "bidirectional"))
    )
    (net (code "80") (name "unconnected-(M6-PAD2-PadP$4)") (class "Default")
      (node (ref "M6") (pin "P$4") (pinfunction "PAD2_P$4") (pintype "bidirectional"))
    )
    (net (code "81") (name "unconnected-(M7-PAD1-PadP$3)") (class "Default")
      (node (ref "M7") (pin "P$3") (pinfunction "PAD1_P$3") (pintype "bidirectional"))
    )
    (net (code "82") (name "unconnected-(M7-PAD2-PadP$4)") (class "Default")
      (node (ref "M7") (pin "P$4") (pinfunction "PAD2_P$4") (pintype "bidirectional"))
    )
  )
)
